# 28Pins.net
KiCad netlist of a schematic drawn in Altium Designer
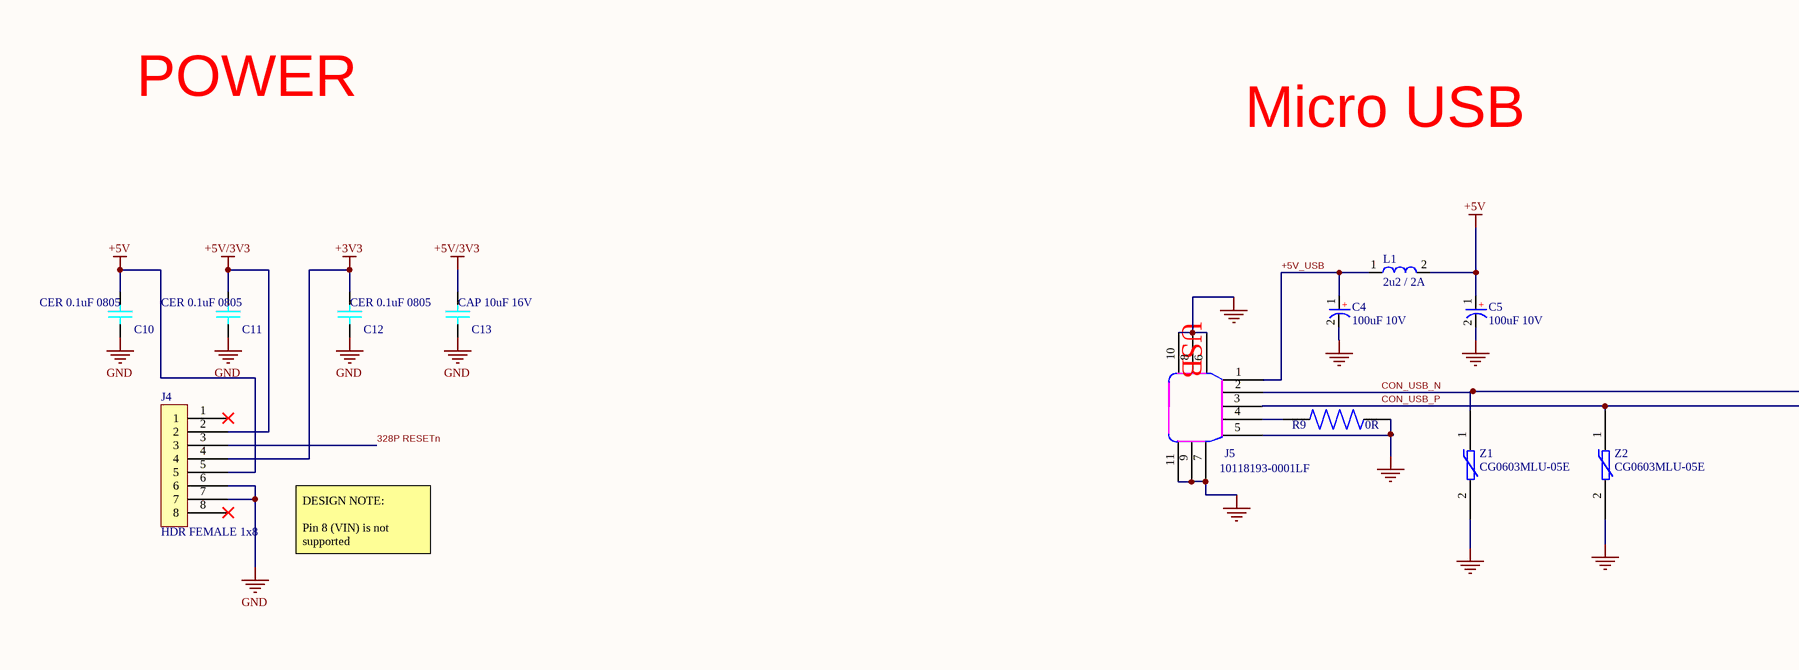
[diagram p0: 28Pins.SchDoc, top left]
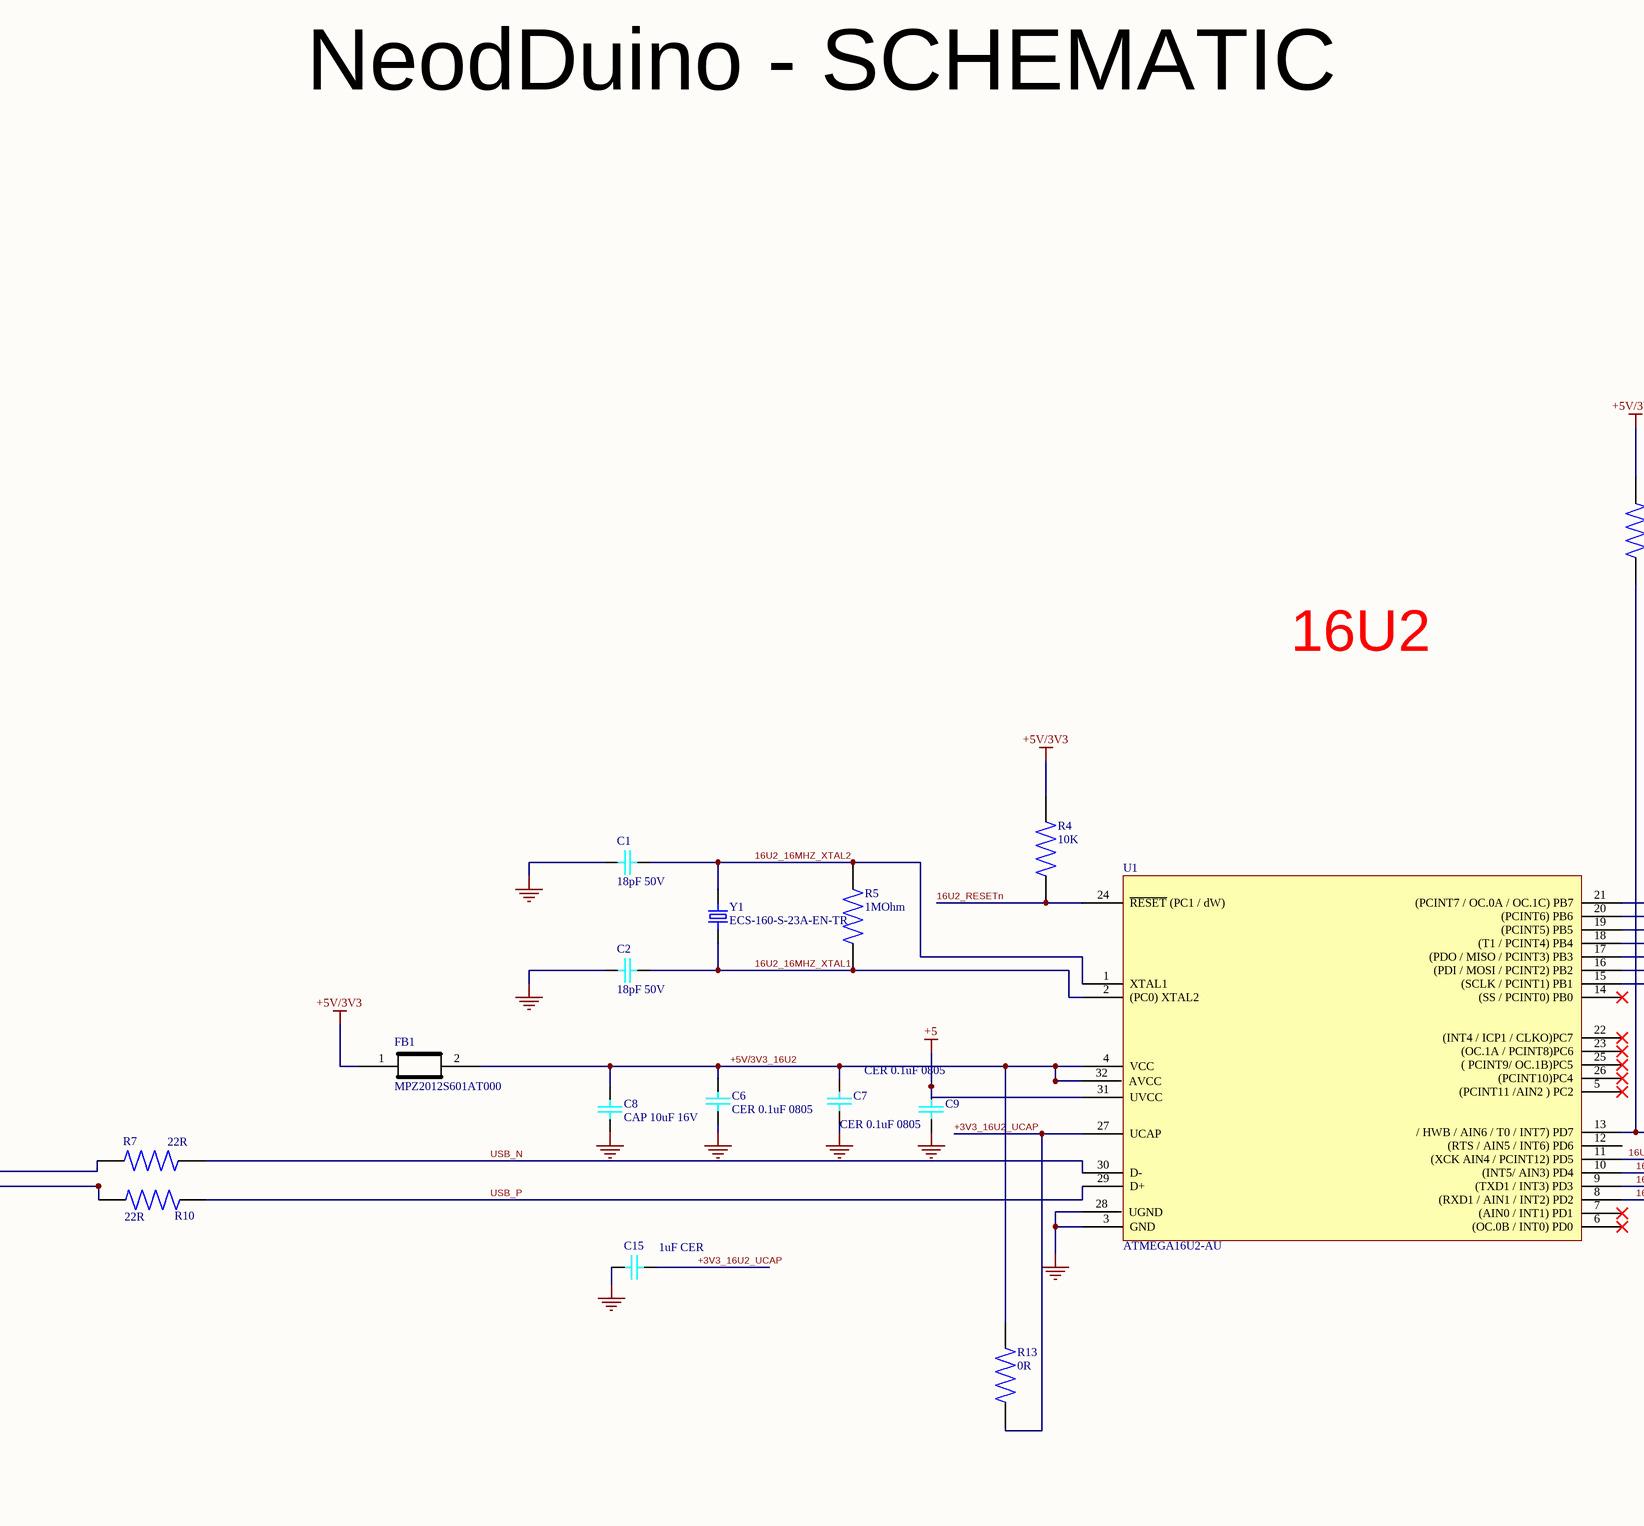
[diagram p1: 28Pins.SchDoc, top middle]
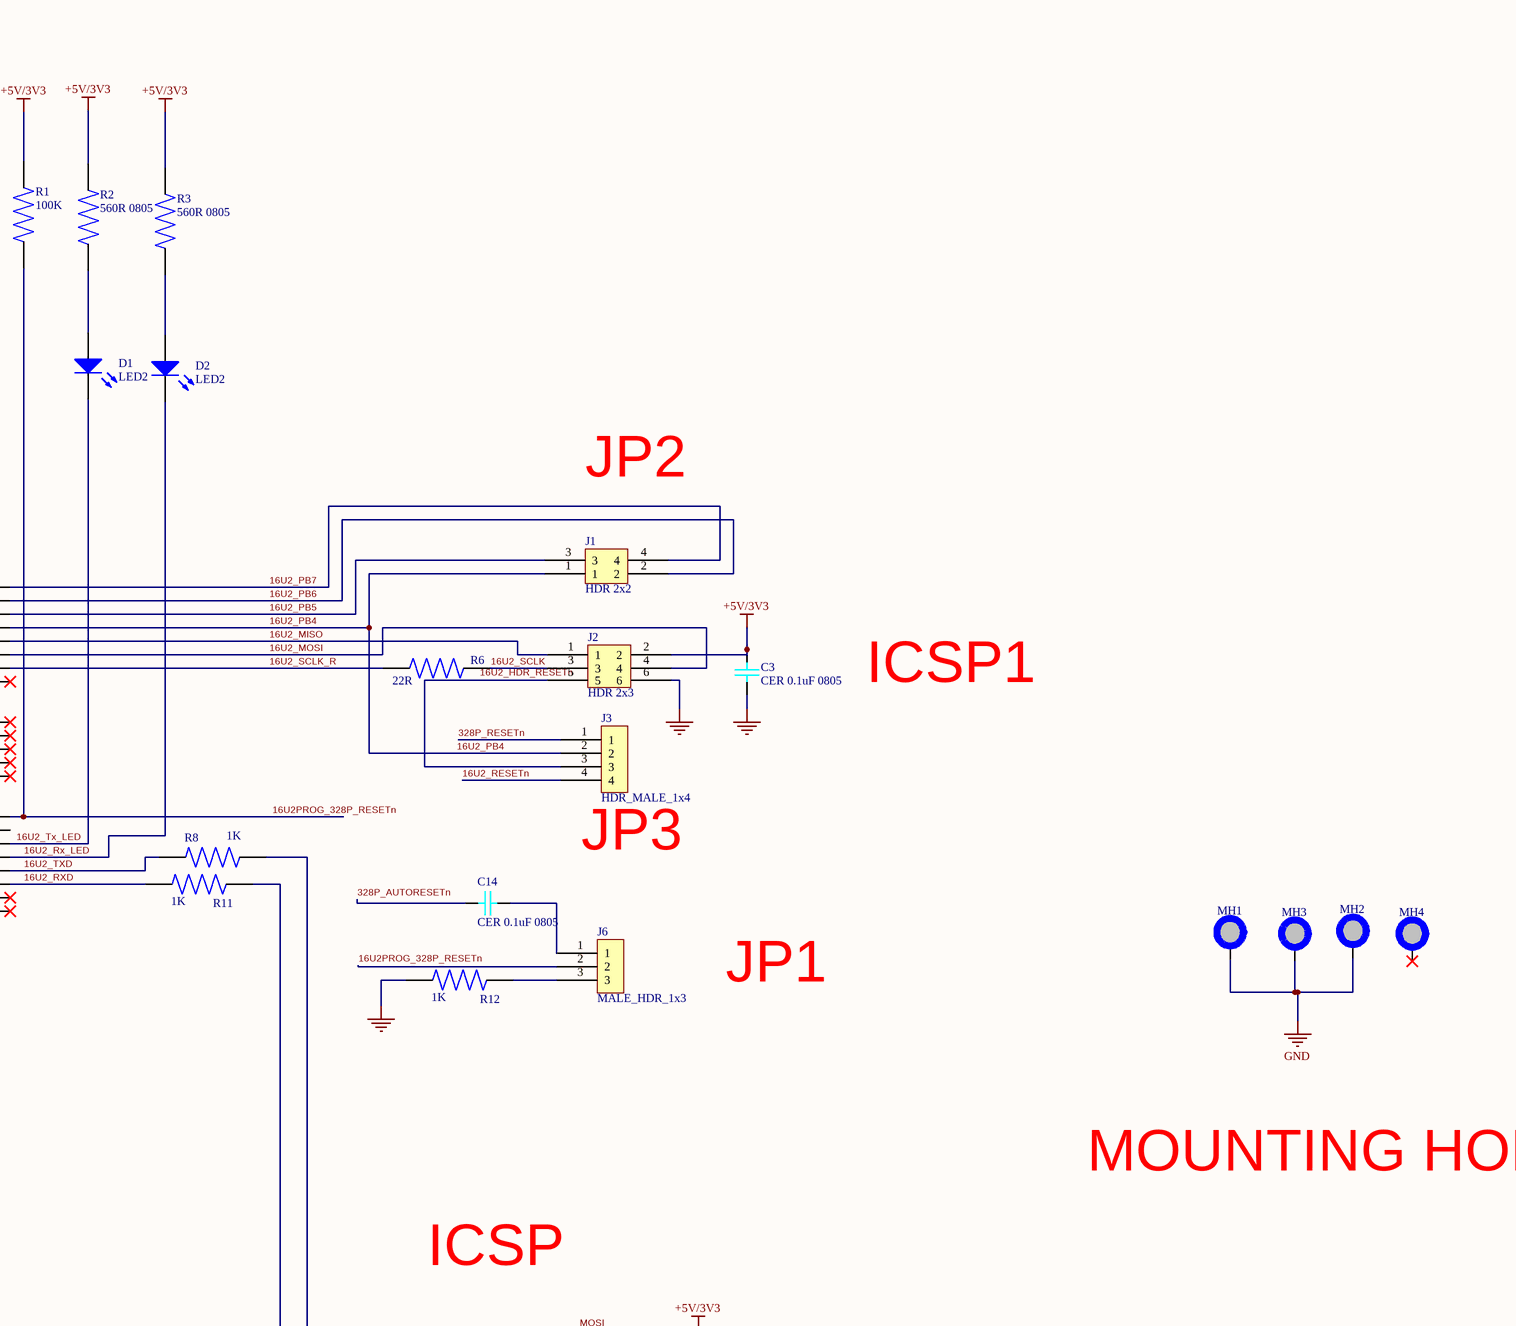
[diagram p2: 28Pins.SchDoc, top right]
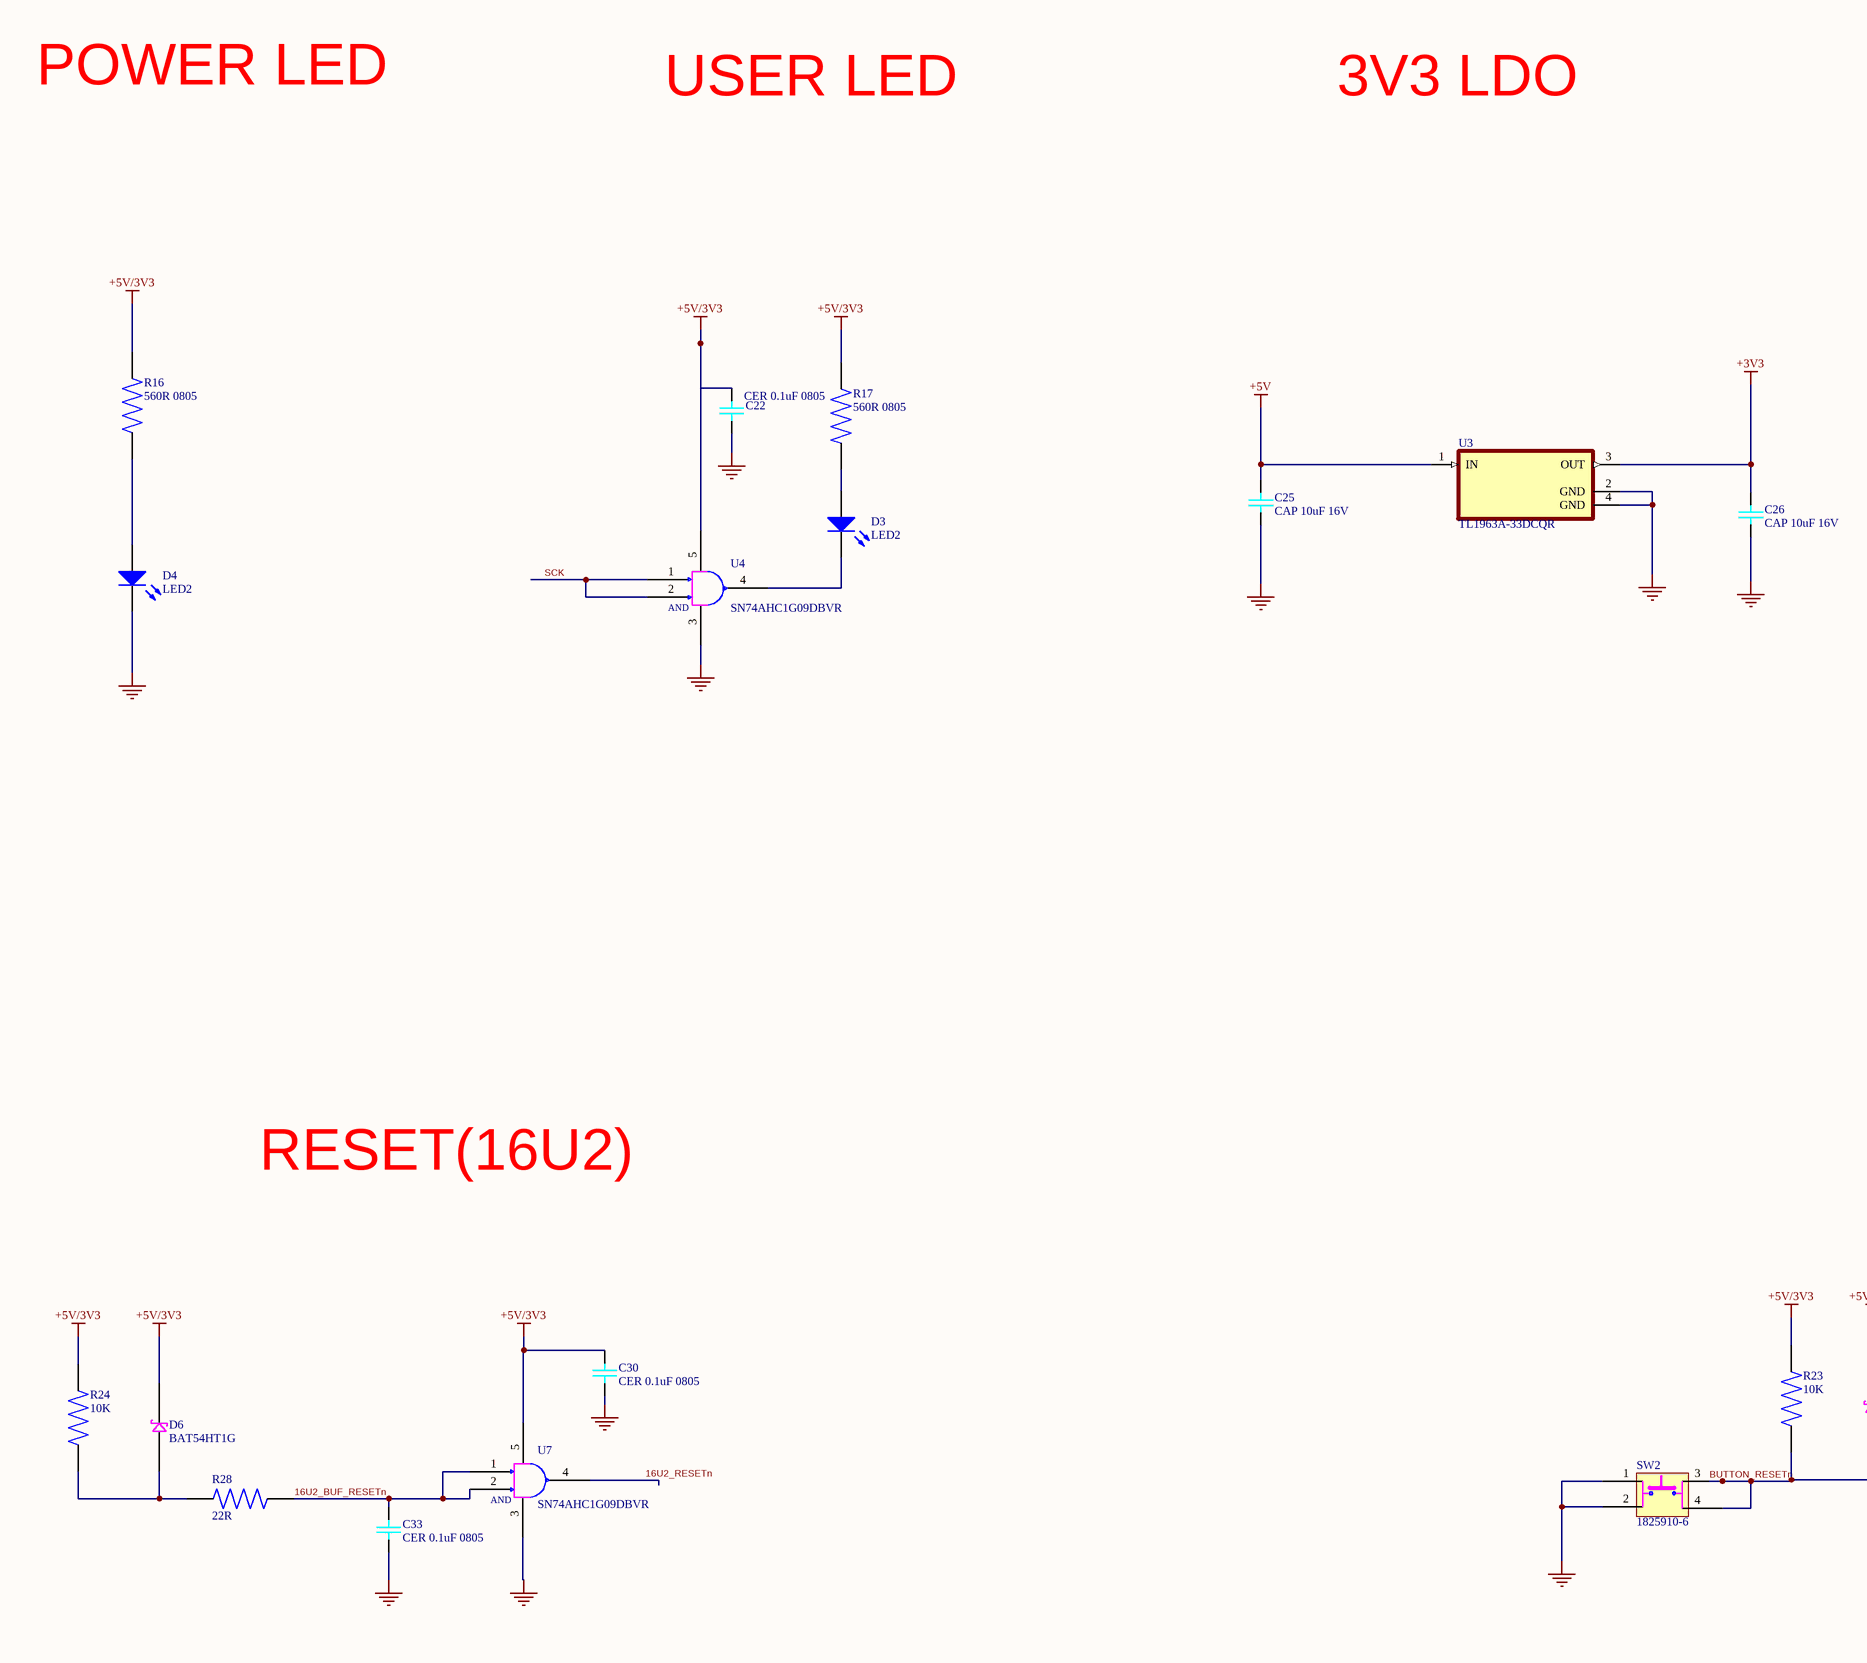
[diagram p3: 28Pins.SchDoc, bottom left]
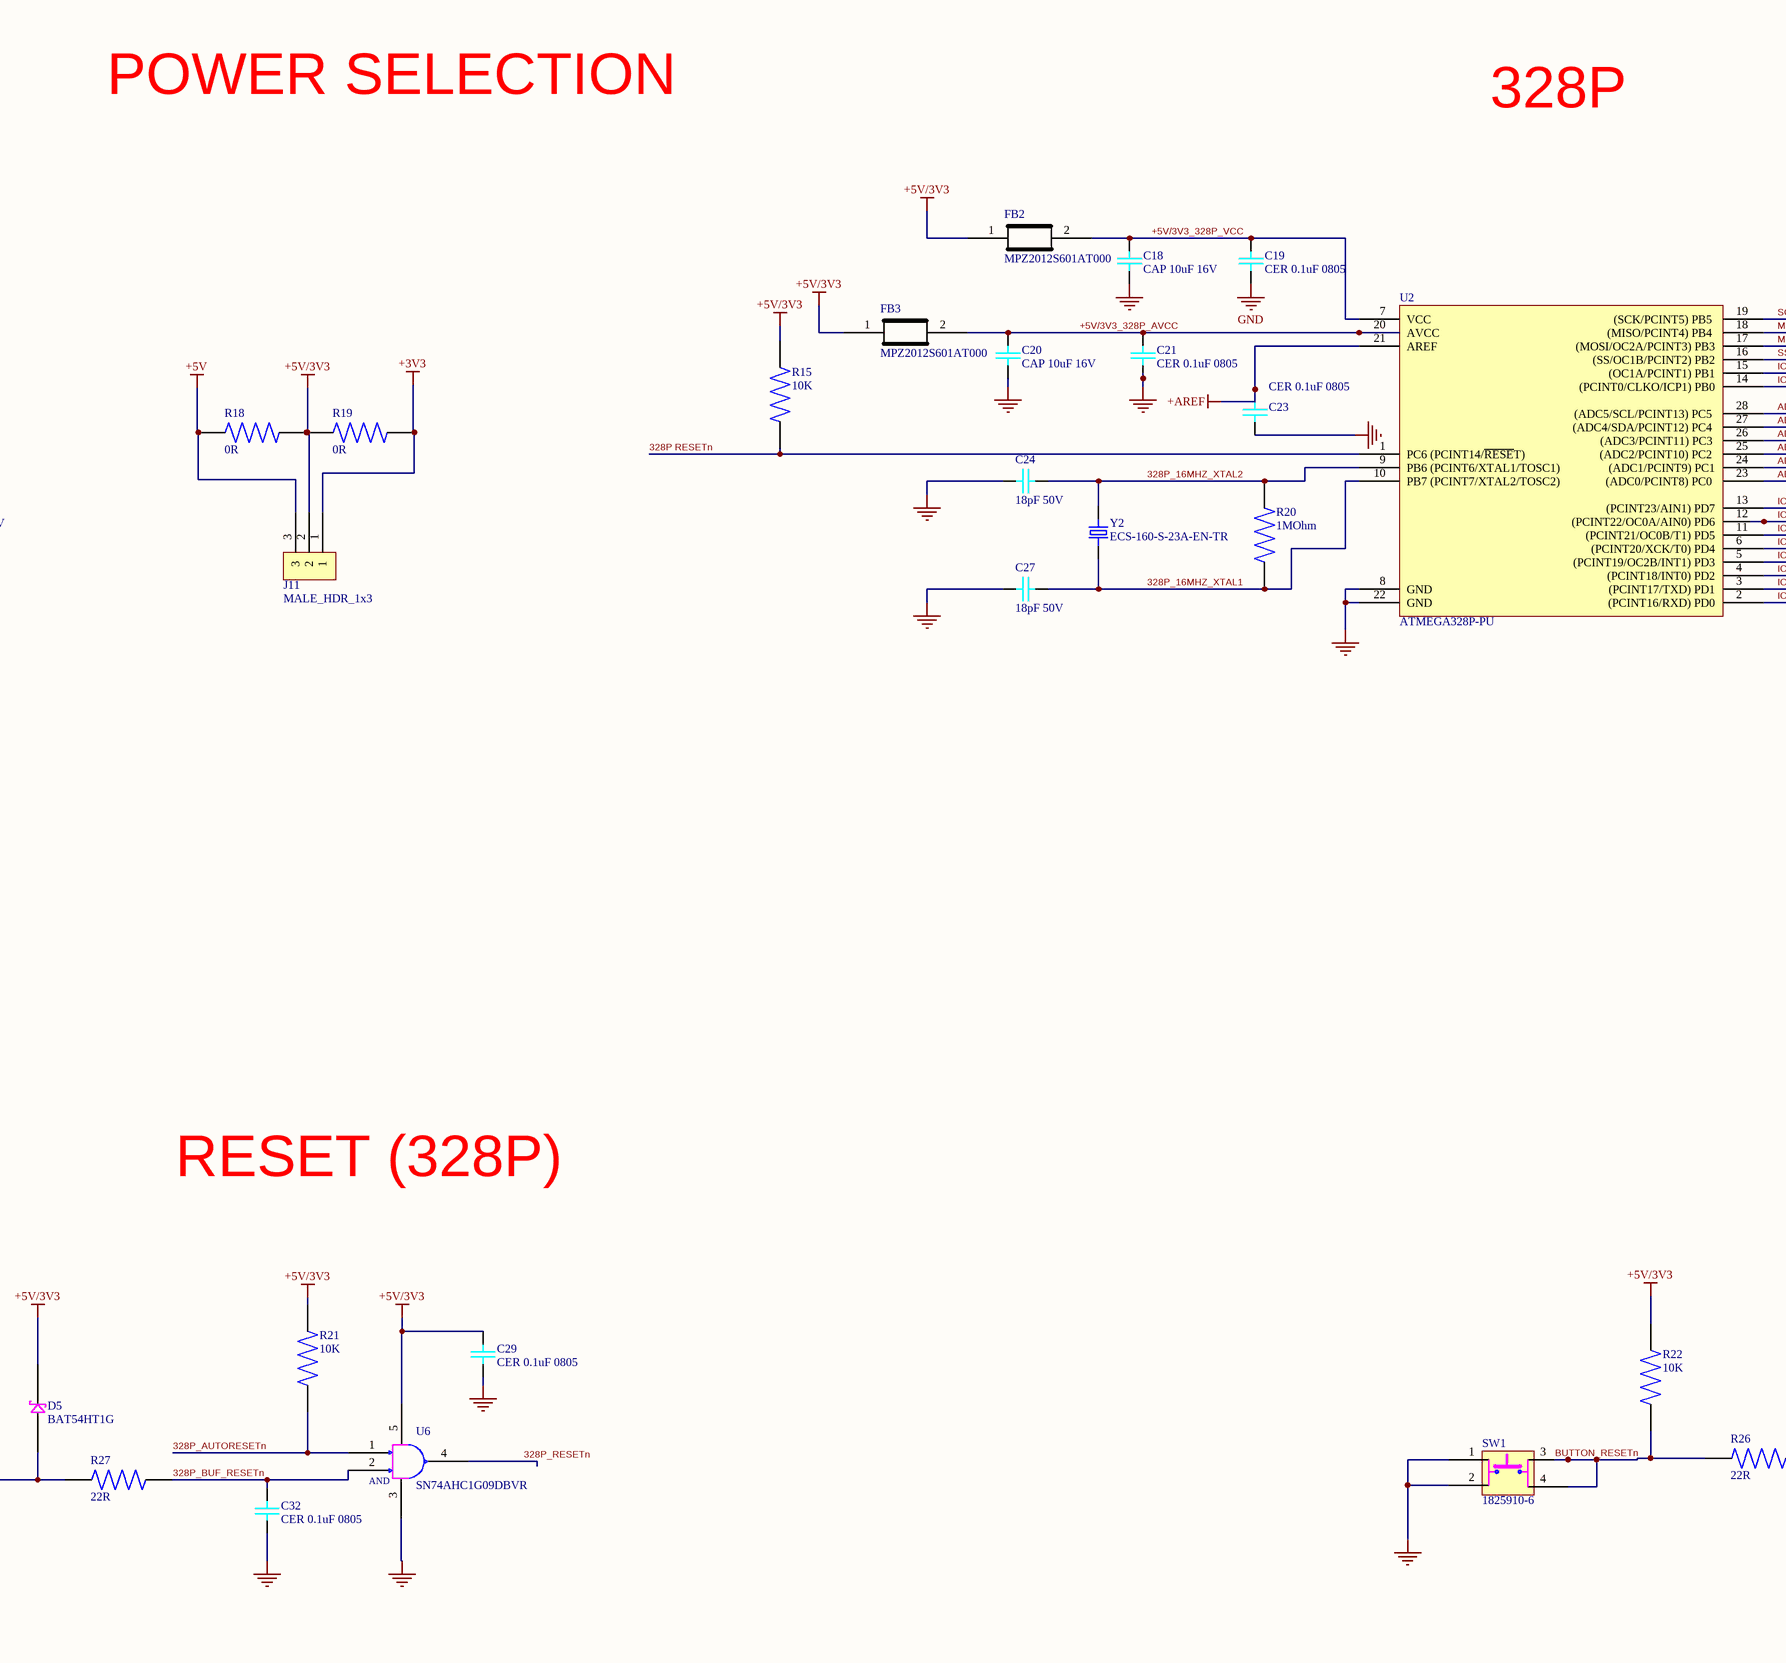
[diagram p4: 28Pins.SchDoc, bottom middle]
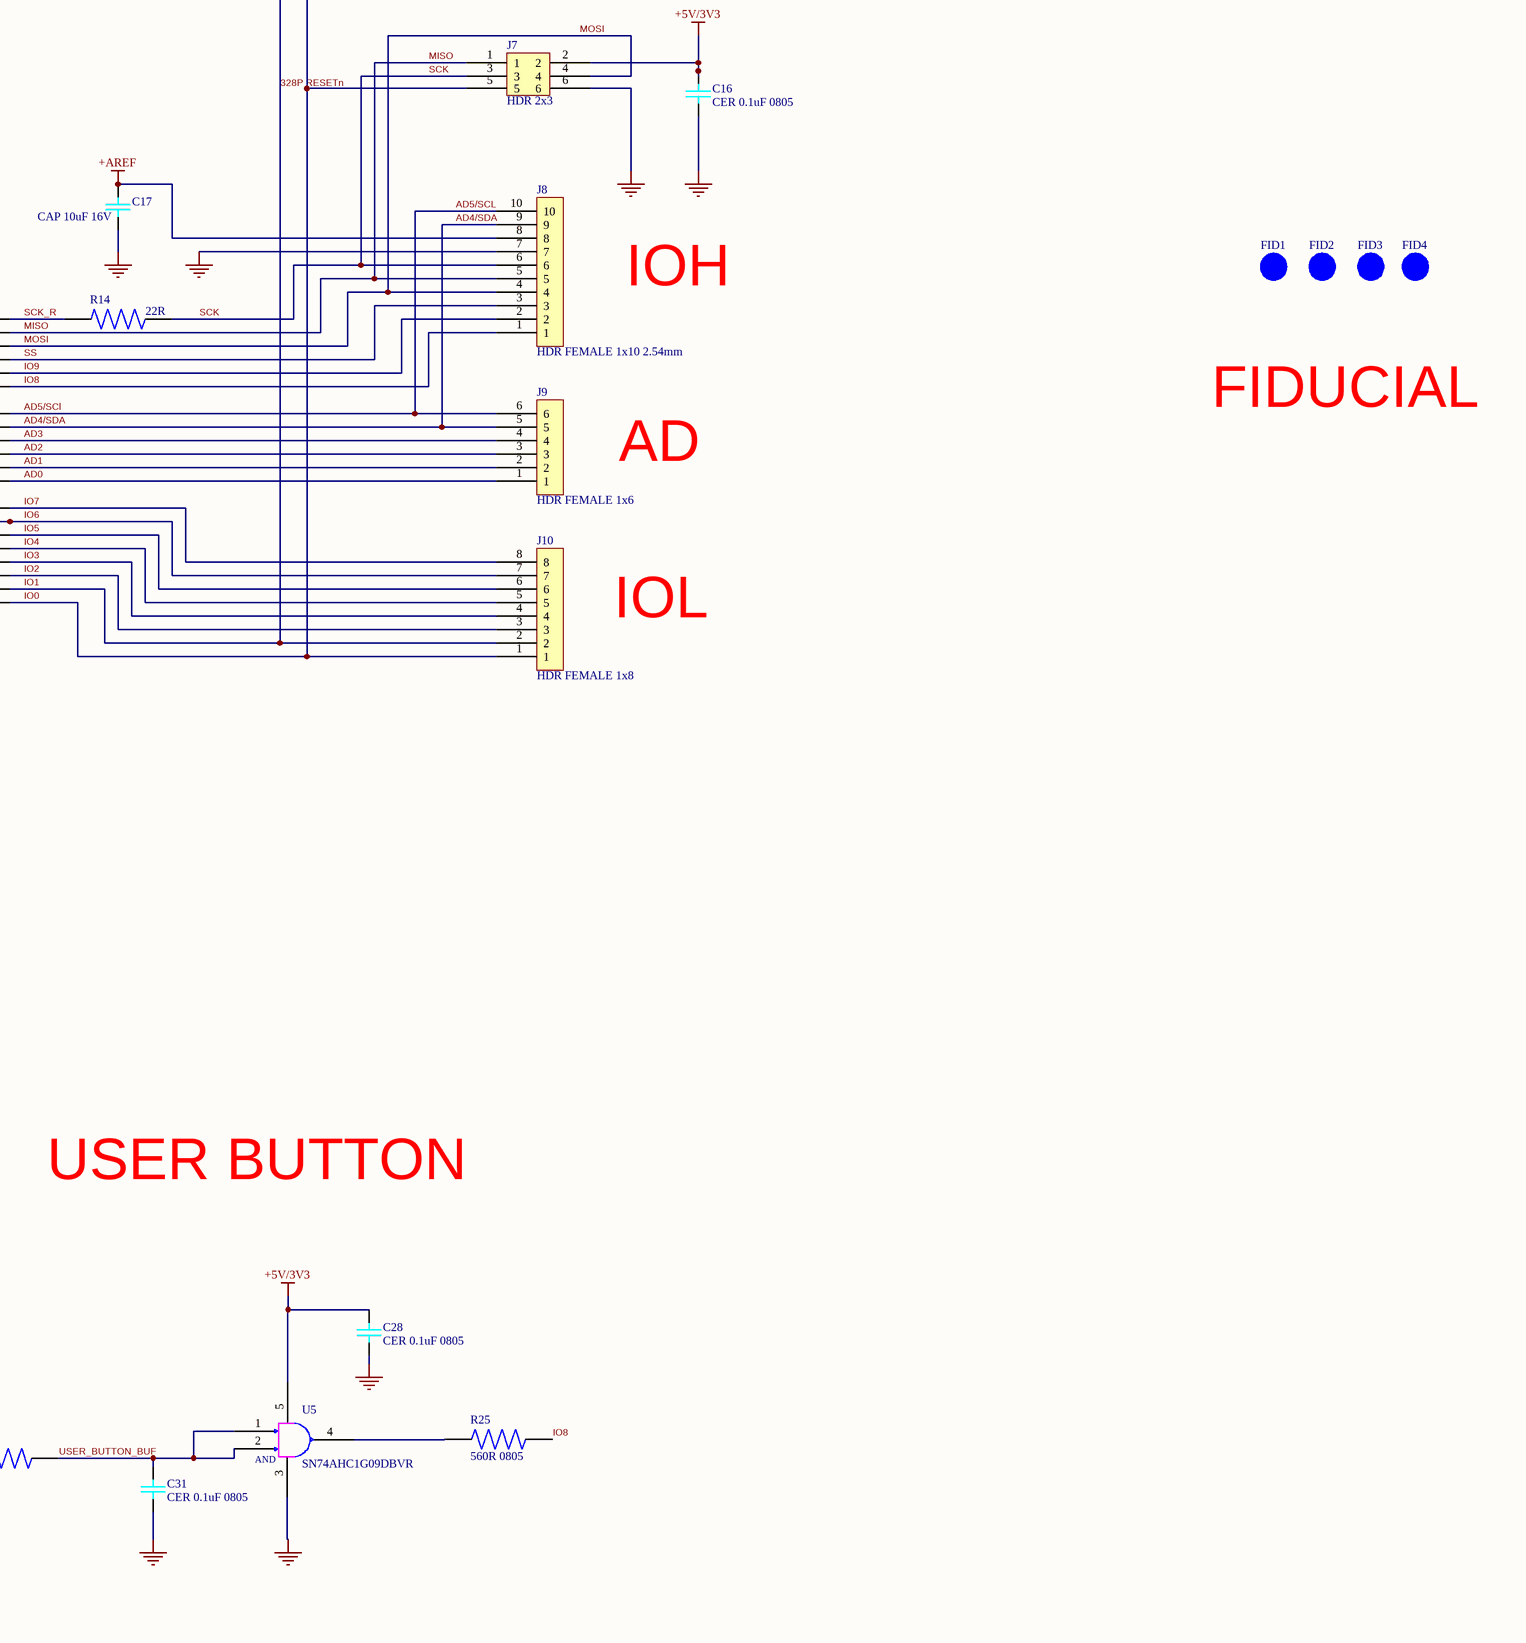
[diagram p5: 28Pins.SchDoc, bottom right]

(export (version "E")
  (design (tool "Eeschema 10.0.6"))
  (components
    (comp (ref "C1")
      (value "18pF 50V")
      (footprint "C0805")
      (fields
        (field (name "MANUFACTURER") "KEMET")
        (field (name "MANUFACTURER PART NUMBER") "C0805C180K5GACTU")
        (field (name "TOLERANCE") "10%")
      )
      (libsource (lib "28Pin_Schlib") (part "C0805C180K5GACTU"))
    )
    (comp (ref "C2")
      (value "18pF 50V")
      (footprint "C0805")
      (fields
        (field (name "MANUFACTURER") "KEMET")
        (field (name "MANUFACTURER PART NUMBER") "C0805C180K5GACTU")
        (field (name "TOLERANCE") "10%")
      )
      (libsource (lib "28Pin_Schlib") (part "C0805C180K5GACTU"))
    )
    (comp (ref "C3")
      (value "CER 0.1uF 0805")
      (footprint "C0805")
      (description "CAP CER 0.1UF 50V X7R 0805")
      (fields
        (field (name "MANUFACTURER") "TDK")
        (field (name "MANUFACTURER PART NUMBER") "CGA4J2X7R1H104K125AE")
      )
      (libsource (lib "28Pin_Schlib") (part "CGA4J2X7R1H104K125AE"))
    )
    (comp (ref "C4")
      (value "100uF 10V")
      (footprint "C_ALUMINIUM_100u")
      (description "CAP ALUM 100UF 20% 10V SMD")
      (fields
        (field (name "MANUFACTURER") "Panasonic")
        (field (name "MANUFACTURER PART NUMBER") "EEE-HA1A101P")
      )
      (libsource (lib "") (part "EEE-HA1A101P_1"))
    )
    (comp (ref "C5")
      (value "100uF 10V")
      (footprint "C_ALUMINIUM_100u")
      (description "CAP ALUM 100UF 20% 10V SMD")
      (fields
        (field (name "MANUFACTURER") "Panasonic")
        (field (name "MANUFACTURER PART NUMBER") "EEE-HA1A101P")
      )
      (libsource (lib "28Pin_Schlib") (part "EEE-HA1A101P"))
    )
    (comp (ref "C6")
      (value "CER 0.1uF 0805")
      (footprint "C0805")
      (description "CAP CER 0.1UF 50V X7R 0805")
      (fields
        (field (name "MANUFACTURER") "TDK")
        (field (name "MANUFACTURER PART NUMBER") "CGA4J2X7R1H104K125AE")
      )
      (libsource (lib "28Pin_Schlib") (part "CGA4J2X7R1H104K125AE"))
    )
    (comp (ref "C7")
      (value "CER 0.1uF 0805")
      (footprint "C0805")
      (description "CAP CER 0.1UF 50V X7R 0805")
      (fields
        (field (name "MANUFACTURER") "TDK")
        (field (name "MANUFACTURER PART NUMBER") "CGA4J2X7R1H104K125AE")
      )
      (libsource (lib "28Pin_Schlib") (part "CGA4J2X7R1H104K125AE"))
    )
    (comp (ref "C8")
      (value "CAP 10uF 16V")
      (footprint "C0805_10uF")
      (fields
        (field (name "MANUFACTURER") "TDK")
        (field (name "MANUFACTURER PART NUMBER") "CGA4J1X5R1C106K125AC")
        (field (name "TOLERANCE") "10%")
      )
      (libsource (lib "28Pin_Schlib") (part "CGA4J1X5R1C106K125AC"))
    )
    (comp (ref "C9")
      (value "CER 0.1uF 0805")
      (footprint "C0805")
      (description "CAP CER 0.1UF 50V X7R 0805")
      (fields
        (field (name "MANUFACTURER") "TDK")
        (field (name "MANUFACTURER PART NUMBER") "CGA4J2X7R1H104K125AE")
      )
      (libsource (lib "28Pin_Schlib") (part "CGA4J2X7R1H104K125AE"))
    )
    (comp (ref "C10")
      (value "CER 0.1uF 0805")
      (footprint "C0805")
      (description "CAP CER 0.1UF 50V X7R 0805")
      (fields
        (field (name "MANUFACTURER") "TDK")
        (field (name "MANUFACTURER PART NUMBER") "CGA4J2X7R1H104K125AE")
      )
      (libsource (lib "28Pin_Schlib") (part "CGA4J2X7R1H104K125AE"))
    )
    (comp (ref "C11")
      (value "CER 0.1uF 0805")
      (footprint "C0805")
      (description "CAP CER 0.1UF 50V X7R 0805")
      (fields
        (field (name "MANUFACTURER") "TDK")
        (field (name "MANUFACTURER PART NUMBER") "CGA4J2X7R1H104K125AE")
      )
      (libsource (lib "28Pin_Schlib") (part "CGA4J2X7R1H104K125AE"))
    )
    (comp (ref "C12")
      (value "CER 0.1uF 0805")
      (footprint "C0805")
      (description "CAP CER 0.1UF 50V X7R 0805")
      (fields
        (field (name "MANUFACTURER") "TDK")
        (field (name "MANUFACTURER PART NUMBER") "CGA4J2X7R1H104K125AE")
      )
      (libsource (lib "28Pin_Schlib") (part "CGA4J2X7R1H104K125AE"))
    )
    (comp (ref "C13")
      (value "CAP 10uF 16V")
      (footprint "C0805_10uF")
      (fields
        (field (name "MANUFACTURER") "TDK")
        (field (name "MANUFACTURER PART NUMBER") "CGA4J1X5R1C106K125AC")
        (field (name "TOLERANCE") "10%")
      )
      (libsource (lib "28Pin_Schlib") (part "CGA4J1X5R1C106K125AC"))
    )
    (comp (ref "C14")
      (value "CER 0.1uF 0805")
      (footprint "C0805")
      (description "CAP CER 0.1UF 50V X7R 0805")
      (fields
        (field (name "MANUFACTURER") "TDK")
        (field (name "MANUFACTURER PART NUMBER") "CGA4J2X7R1H104K125AE")
      )
      (libsource (lib "28Pin_Schlib") (part "CGA4J2X7R1H104K125AE"))
    )
    (comp (ref "C15")
      (value "1uF CER")
      (footprint "C0805")
      (description "CAP CER 1UF 25V X7R 0805")
      (fields
        (field (name "MANUFACTURER") "TDK")
        (field (name "MANUFACTURER PART NUMBER") "CGA4J3X7R1E105M125AB")
      )
      (libsource (lib "28Pin_Schlib") (part "CGA4J3X7R1E105M125AB"))
    )
    (comp (ref "C16")
      (value "CER 0.1uF 0805")
      (footprint "C0805")
      (description "CAP CER 0.1UF 50V X7R 0805")
      (fields
        (field (name "MANUFACTURER") "TDK")
        (field (name "MANUFACTURER PART NUMBER") "CGA4J2X7R1H104K125AE")
      )
      (libsource (lib "28Pin_Schlib") (part "CGA4J2X7R1H104K125AE"))
    )
    (comp (ref "C17")
      (value "CAP 10uF 16V")
      (footprint "C0805_10uF")
      (fields
        (field (name "MANUFACTURER") "TDK")
        (field (name "MANUFACTURER PART NUMBER") "CGA4J1X5R1C106K125AC")
        (field (name "TOLERANCE") "10%")
      )
      (libsource (lib "28Pin_Schlib") (part "CGA4J1X5R1C106K125AC"))
    )
    (comp (ref "C18")
      (value "CAP 10uF 16V")
      (footprint "C0805_10uF")
      (fields
        (field (name "MANUFACTURER") "TDK")
        (field (name "MANUFACTURER PART NUMBER") "CGA4J1X5R1C106K125AC")
        (field (name "TOLERANCE") "10%")
      )
      (libsource (lib "28Pin_Schlib") (part "CGA4J1X5R1C106K125AC"))
    )
    (comp (ref "C19")
      (value "CER 0.1uF 0805")
      (footprint "C0805")
      (description "CAP CER 0.1UF 50V X7R 0805")
      (fields
        (field (name "MANUFACTURER") "TDK")
        (field (name "MANUFACTURER PART NUMBER") "CGA4J2X7R1H104K125AE")
      )
      (libsource (lib "28Pin_Schlib") (part "CGA4J2X7R1H104K125AE"))
    )
    (comp (ref "C20")
      (value "CAP 10uF 16V")
      (footprint "C0805_10uF")
      (fields
        (field (name "MANUFACTURER") "TDK")
        (field (name "MANUFACTURER PART NUMBER") "CGA4J1X5R1C106K125AC")
        (field (name "TOLERANCE") "10%")
      )
      (libsource (lib "28Pin_Schlib") (part "CGA4J1X5R1C106K125AC"))
    )
    (comp (ref "C21")
      (value "CER 0.1uF 0805")
      (footprint "C0805")
      (description "CAP CER 0.1UF 50V X7R 0805")
      (fields
        (field (name "MANUFACTURER") "TDK")
        (field (name "MANUFACTURER PART NUMBER") "CGA4J2X7R1H104K125AE")
      )
      (libsource (lib "28Pin_Schlib") (part "CGA4J2X7R1H104K125AE"))
    )
    (comp (ref "C22")
      (value "CER 0.1uF 0805")
      (footprint "C0805")
      (description "CAP CER 0.1UF 50V X7R 0805")
      (fields
        (field (name "MANUFACTURER") "TDK")
        (field (name "MANUFACTURER PART NUMBER") "CGA4J2X7R1H104K125AE")
      )
      (libsource (lib "28Pin_Schlib") (part "CGA4J2X7R1H104K125AE"))
    )
    (comp (ref "C23")
      (value "CER 0.1uF 0805")
      (footprint "C0805")
      (description "CAP CER 0.1UF 50V X7R 0805")
      (fields
        (field (name "MANUFACTURER") "TDK")
        (field (name "MANUFACTURER PART NUMBER") "CGA4J2X7R1H104K125AE")
      )
      (libsource (lib "28Pin_Schlib") (part "CGA4J2X7R1H104K125AE"))
    )
    (comp (ref "C24")
      (value "18pF 50V")
      (footprint "C0805")
      (fields
        (field (name "MANUFACTURER") "KEMET")
        (field (name "MANUFACTURER PART NUMBER") "C0805C180K5GACTU")
        (field (name "TOLERANCE") "10%")
      )
      (libsource (lib "28Pin_Schlib") (part "C0805C180K5GACTU"))
    )
    (comp (ref "C25")
      (value "CAP 10uF 16V")
      (footprint "C0805_10uF")
      (fields
        (field (name "MANUFACTURER") "TDK")
        (field (name "MANUFACTURER PART NUMBER") "CGA4J1X5R1C106K125AC")
        (field (name "TOLERANCE") "10%")
      )
      (libsource (lib "28Pin_Schlib") (part "CGA4J1X5R1C106K125AC"))
    )
    (comp (ref "C26")
      (value "CAP 10uF 16V")
      (footprint "C0805_10uF")
      (fields
        (field (name "MANUFACTURER") "TDK")
        (field (name "MANUFACTURER PART NUMBER") "CGA4J1X5R1C106K125AC")
        (field (name "TOLERANCE") "10%")
      )
      (libsource (lib "28Pin_Schlib") (part "CGA4J1X5R1C106K125AC"))
    )
    (comp (ref "C27")
      (value "18pF 50V")
      (footprint "C0805")
      (fields
        (field (name "MANUFACTURER") "KEMET")
        (field (name "MANUFACTURER PART NUMBER") "C0805C180K5GACTU")
        (field (name "TOLERANCE") "10%")
      )
      (libsource (lib "28Pin_Schlib") (part "C0805C180K5GACTU"))
    )
    (comp (ref "C28")
      (value "CER 0.1uF 0805")
      (footprint "C0805")
      (description "CAP CER 0.1UF 50V X7R 0805")
      (fields
        (field (name "MANUFACTURER") "TDK")
        (field (name "MANUFACTURER PART NUMBER") "CGA4J2X7R1H104K125AE")
      )
      (libsource (lib "28Pin_Schlib") (part "CGA4J2X7R1H104K125AE"))
    )
    (comp (ref "C29")
      (value "CER 0.1uF 0805")
      (footprint "C0805")
      (description "CAP CER 0.1UF 50V X7R 0805")
      (fields
        (field (name "MANUFACTURER") "TDK")
        (field (name "MANUFACTURER PART NUMBER") "CGA4J2X7R1H104K125AE")
      )
      (libsource (lib "28Pin_Schlib") (part "CGA4J2X7R1H104K125AE"))
    )
    (comp (ref "C30")
      (value "CER 0.1uF 0805")
      (footprint "C0805")
      (description "CAP CER 0.1UF 50V X7R 0805")
      (fields
        (field (name "MANUFACTURER") "TDK")
        (field (name "MANUFACTURER PART NUMBER") "CGA4J2X7R1H104K125AE")
      )
      (libsource (lib "28Pin_Schlib") (part "CGA4J2X7R1H104K125AE"))
    )
    (comp (ref "C31")
      (value "CER 0.1uF 0805")
      (footprint "C0805")
      (description "CAP CER 0.1UF 50V X7R 0805")
      (fields
        (field (name "MANUFACTURER") "TDK")
        (field (name "MANUFACTURER PART NUMBER") "CGA4J2X7R1H104K125AE")
      )
      (libsource (lib "28Pin_Schlib") (part "CGA4J2X7R1H104K125AE"))
    )
    (comp (ref "C32")
      (value "CER 0.1uF 0805")
      (footprint "C0805")
      (description "CAP CER 0.1UF 50V X7R 0805")
      (fields
        (field (name "MANUFACTURER") "TDK")
        (field (name "MANUFACTURER PART NUMBER") "CGA4J2X7R1H104K125AE")
      )
      (libsource (lib "28Pin_Schlib") (part "CGA4J2X7R1H104K125AE"))
    )
    (comp (ref "C33")
      (value "CER 0.1uF 0805")
      (footprint "C0805")
      (description "CAP CER 0.1UF 50V X7R 0805")
      (fields
        (field (name "MANUFACTURER") "TDK")
        (field (name "MANUFACTURER PART NUMBER") "CGA4J2X7R1H104K125AE")
      )
      (libsource (lib "28Pin_Schlib") (part "CGA4J2X7R1H104K125AE"))
    )
    (comp (ref "D1")
      (value "LED2")
      (footprint "3.2X1.6X1.1")
      (description "Typical RED, GREEN, YELLOW, AMBER GaAs LED")
      (fields (field (name "PUBLISHER") "Altium Limited"))
      (libsource (lib "Miscellaneous Devices") (part "LED2"))
    )
    (comp (ref "D2")
      (value "LED2")
      (footprint "3.2X1.6X1.1")
      (description "Typical RED, GREEN, YELLOW, AMBER GaAs LED")
      (fields (field (name "PUBLISHER") "Altium Limited"))
      (libsource (lib "Miscellaneous Devices") (part "LED2"))
    )
    (comp (ref "D3")
      (value "LED2")
      (footprint "3.2X1.6X1.1")
      (description "Typical RED, GREEN, YELLOW, AMBER GaAs LED")
      (fields (field (name "PUBLISHER") "Altium Limited"))
      (libsource (lib "Miscellaneous Devices") (part "LED2"))
    )
    (comp (ref "D4")
      (value "LED2")
      (footprint "3.2X1.6X1.1")
      (description "Typical RED, GREEN, YELLOW, AMBER GaAs LED")
      (fields (field (name "PUBLISHER") "Altium Limited"))
      (libsource (lib "Miscellaneous Devices") (part "LED2"))
    )
    (comp (ref "D5")
      (value "BAT54HT1G")
      (footprint "SOD323_DIODE")
      (description "Small Signal Schottky Diode, Single, 30 V, 200 mA, 800 mV, 600 mA, 150 C ;RoHS Compliant: Yes")
      (fields (field (name "MANUFACTURER") "ON Semiconductor / Fairchild"))
      (libsource (lib "28Pin_Schlib") (part "BAT54HT1G"))
    )
    (comp (ref "D6")
      (value "BAT54HT1G")
      (footprint "SOD323_DIODE")
      (description "Small Signal Schottky Diode, Single, 30 V, 200 mA, 800 mV, 600 mA, 150 C ;RoHS Compliant: Yes")
      (fields (field (name "MANUFACTURER") "ON Semiconductor / Fairchild"))
      (libsource (lib "28Pin_Schlib") (part "BAT54HT1G"))
    )
    (comp (ref "FB1")
      (value "MPZ2012S601AT000")
      (footprint "C0805")
      (description "FERRITE BEAD 600 OHM 0805 1LN")
      (fields (field (name "MANUFACTURER") "TDK"))
      (libsource (lib "28Pin_Schlib") (part "MPZ2012S601AT000"))
    )
    (comp (ref "FB2")
      (value "MPZ2012S601AT000")
      (footprint "C0805")
      (description "FERRITE BEAD 600 OHM 0805 1LN")
      (fields (field (name "MANUFACTURER") "TDK"))
      (libsource (lib "28Pin_Schlib") (part "MPZ2012S601AT000"))
    )
    (comp (ref "FB3")
      (value "MPZ2012S601AT000")
      (footprint "C0805")
      (description "FERRITE BEAD 600 OHM 0805 1LN")
      (fields (field (name "MANUFACTURER") "TDK"))
      (libsource (lib "28Pin_Schlib") (part "MPZ2012S601AT000"))
    )
    (comp (ref "FID1")
      (value "FID_1MMC")
      (footprint "FID_40x120MM")
      (description "Fiducial 40mil dia, 120mil mask")
      (libsource (lib "28Pin_Schlib") (part "FID_1MM"))
    )
    (comp (ref "FID2")
      (value "FID_1MMC")
      (footprint "FID_40x120MM")
      (description "Fiducial 40mil dia, 120mil mask")
      (libsource (lib "28Pin_Schlib") (part "FID_1MM"))
    )
    (comp (ref "FID3")
      (value "FID_1MMC")
      (footprint "FID_40x120MM")
      (description "Fiducial 40mil dia, 120mil mask")
      (libsource (lib "28Pin_Schlib") (part "FID_1MM"))
    )
    (comp (ref "FID4")
      (value "FID_1MMC")
      (footprint "FID_40x120MM")
      (description "Fiducial 40mil dia, 120mil mask")
      (libsource (lib "28Pin_Schlib") (part "FID_1MM"))
    )
    (comp (ref "J1")
      (value "HDR 2x2")
      (footprint "HDR_2x2_2.54MM")
      (description "02+02 DIL Vert Pin Hdr")
      (fields (field (name "MANUFACTURER") "Harwin") (field (name "MANUFACTURER PART NUMBER") "M20-9980245"))
      (libsource (lib "28Pin_Schlib") (part "M20-9980245"))
    )
    (comp (ref "J2")
      (value "HDR 2x3")
      (footprint "HDR_2x3_2.54MM")
      (description "Conn Unshrouded Header HDR 6 POS 2.54mm Solder ST Thru-Hole Bag")
      (fields (field (name "MANUFACTURER") "Harwin") (field (name "MANUFACTURER PART NUMBER") "M20-9980346"))
      (libsource (lib "28Pin_Schlib") (part "M20-9980346"))
    )
    (comp (ref "J3")
      (value "HDR_MALE_1x4")
      (footprint "HDR_MALE_1x4")
      (description "4 Way Sil Horiz Smt P/hdr Rohs Compliant: Yes")
      (fields (field (name "MANUFACTURER") "Harwin") (field (name "MANUFACTURER PART NUMBER") "M20-8890445"))
      (libsource (lib "28Pin_Schlib") (part "M20-8890445"))
    )
    (comp (ref "J4")
      (value "HDR FEMALE 1x8")
      (footprint "HDR_FEMALE_1x8")
      (fields (field (name "MANUFACTURER") "Harwin") (field (name "MANUFACTURER PART NUMBER") "M20-7821046"))
      (libsource (lib "") (part "M20-7821046_1"))
    )
    (comp (ref "J5")
      (value "10118193-0001LF")
      (footprint "USB_micro")
      (description "CONN USB MICRO B RECPT SMT R/A")
      (fields (field (name "MANUFACTURER") "Amphenol ICC / FCI"))
      (libsource (lib "28Pin_Schlib") (part "10118193-0001LF"))
    )
    (comp (ref "J6")
      (value "MALE_HDR_1x3")
      (footprint "HDR_MALE_1x3")
      (fields (field (name "MANUFACTURER") "Harwin") (field (name "MANUFACTURER PART NUMBER") "M20-9990345"))
      (libsource (lib "") (part "M20-9990345_1"))
    )
    (comp (ref "J7")
      (value "HDR 2x3")
      (footprint "HDR_2x3_2.54MM")
      (description "Conn Unshrouded Header HDR 6 POS 2.54mm Solder ST Thru-Hole Bag")
      (fields (field (name "MANUFACTURER") "Harwin") (field (name "MANUFACTURER PART NUMBER") "M20-9980346"))
      (libsource (lib "28Pin_Schlib") (part "M20-9980346"))
    )
    (comp (ref "J8")
      (value "HDR FEMALE 1x10 2.54mm")
      (footprint "HDR_FEMALE_1x10")
      (libsource (lib "28Pin_Schlib") (part "952-3580-ND (female header 10pin)"))
    )
    (comp (ref "J9")
      (value "HDR FEMALE 1x6")
      (footprint "HDR_FEMALE_1x6")
      (description "06-WAY SIL VERT SOCKET L/FREE")
      (fields (field (name "MANUFACTURER") "Harwin") (field (name "MANUFACTURER PART NUMBER") "M20-7820646"))
      (libsource (lib "28Pin_Schlib") (part "M20-7820646"))
    )
    (comp (ref "J10")
      (value "HDR FEMALE 1x8")
      (footprint "HDR_FEMALE_1x8")
      (fields (field (name "MANUFACTURER") "Harwin") (field (name "MANUFACTURER PART NUMBER") "M20-7821046"))
      (libsource (lib "28Pin_Schlib") (part "M20-7821046"))
    )
    (comp (ref "J11")
      (value "MALE_HDR_1x3")
      (footprint "HDR_MALE_1x3")
      (fields (field (name "MANUFACTURER") "Harwin") (field (name "MANUFACTURER PART NUMBER") "M20-9990345"))
      (libsource (lib "28Pin_Schlib") (part "M20-9990345"))
    )
    (comp (ref "L1")
      (value "2u2 / 2A")
      (footprint "CL10INDUCTOR")
      (description "FIXED IND 2.2UH 2A 80 MOHM SMD")
      (fields
        (field (name "MANUFACTURER") "KEMET")
        (field (name "MANUFACTURER PART NUMBER") "L1210R2R2MDWIT")
      )
      (libsource (lib "28Pin_Schlib") (part "L1210R2R2MDWIT"))
    )
    (comp (ref "MH1")
      (value "MH_7.4_3.3MM")
      (footprint "MH_7.4MM_3.2MMDRILL_NOPT")
      (description "Mounting hole 7.4mm diameter, 3.4 mm drill")
      (libsource (lib "28Pin_Schlib") (part "mounting_holes"))
    )
    (comp (ref "MH2")
      (value "MH_7.4_3.3MM")
      (footprint "MH_7.4MM_3.2MMDRILL_NOPT")
      (description "Mounting hole 7.4mm diameter, 3.4 mm drill")
      (libsource (lib "28Pin_Schlib") (part "mounting_holes"))
    )
    (comp (ref "MH3")
      (value "MH_7.4_3.3MM")
      (footprint "MH_7.4MM_3.2MMDRILL_NOPT")
      (description "Mounting hole 7.4mm diameter, 3.4 mm drill")
      (libsource (lib "28Pin_Schlib") (part "mounting_holes"))
    )
    (comp (ref "MH4")
      (value "MH_7.4_3.3MM")
      (footprint "MH_7.4MM_3.2MMDRILL_NOPT")
      (description "Mounting hole 7.4mm diameter, 3.4 mm drill")
      (libsource (lib "28Pin_Schlib") (part "mounting_holes"))
    )
    (comp (ref "R1")
      (value "100K")
      (footprint "RESC2012X65N")
      (description "Res Thick Film 0805 100K Ohm 1% 1/8W ±100ppm/°C Molded SMD SMD Paper T/R")
      (fields
        (field (name "MANUFACTURER") "Yageo")
        (field (name "MANUFACTURER PART NUMBER") "AC0805FR-07100KL")
      )
      (libsource (lib "28Pin_Schlib") (part "AC0805FR-07100KL"))
    )
    (comp (ref "R2")
      (value "560R 0805")
      (footprint "RESC2012X65N")
      (description "RES SMD 560 OHM 1% 1/8W 0805")
      (fields
        (field (name "MANUFACTURER") "Yageo")
        (field (name "MANUFACTURER PART NUMBER") "RT0805FRE07560RL")
      )
      (libsource (lib "28Pin_Schlib") (part "RT0805FRE07560RL"))
    )
    (comp (ref "R3")
      (value "560R 0805")
      (footprint "RESC2012X65N")
      (description "RES SMD 560 OHM 1% 1/8W 0805")
      (fields
        (field (name "MANUFACTURER") "Yageo")
        (field (name "MANUFACTURER PART NUMBER") "RT0805FRE07560RL")
      )
      (libsource (lib "28Pin_Schlib") (part "RT0805FRE07560RL"))
    )
    (comp (ref "R4")
      (value "10K")
      (footprint "RESC2012X65N")
      (description "RES SMD 10K OHM 1% 1/8W 0805")
      (fields
        (field (name "MANUFACTURER") "Yageo")
        (field (name "MANUFACTURER PART NUMBER") "AC0805FR-0710KL")
      )
      (libsource (lib "28Pin_Schlib") (part "AC0805FR-0710KL"))
    )
    (comp (ref "R5")
      (value "1MOhm")
      (footprint "RESC2012X65N")
      (fields (field (name "MP") "RMCF0805FG1M00"))
      (libsource (lib "RMCF0805FG1M00") (part "RMCF0805FG1M00"))
    )
    (comp (ref "R6")
      (value "22R")
      (footprint "RESC2012X65N")
      (description "Resistor;  Thick Film;  Res 22 Ohms;  Pwr-Rtg0.125 W;  Tol 1%;  SMT;  0805")
      (fields
        (field (name "MANUFACTURER") "TE Connectivity")
        (field (name "MANUFACTURER PART NUMBER") "CRG0805F22R")
      )
      (libsource (lib "28Pin_Schlib") (part "CRG0805F22R"))
    )
    (comp (ref "R7")
      (value "22R")
      (footprint "RESC2012X65N")
      (description "Resistor;  Thick Film;  Res 22 Ohms;  Pwr-Rtg0.125 W;  Tol 1%;  SMT;  0805")
      (fields
        (field (name "MANUFACTURER") "TE Connectivity")
        (field (name "MANUFACTURER PART NUMBER") "CRG0805F22R")
      )
      (libsource (lib "28Pin_Schlib") (part "CRG0805F22R"))
    )
    (comp (ref "R8")
      (value "1K")
      (footprint "RESC2012X65N")
      (fields
        (field (name "MANUFACTURER") "TE Connectivity Neohm")
        (field (name "MANUFACTURER PART NUMBER") "CPF0805B1K0E1")
        (field (name "TOLERANCE") "0.1%")
      )
      (libsource (lib "28Pin_Schlib") (part "CPF0805B1K0E1"))
    )
    (comp (ref "R9")
      (value "0R")
      (footprint "RESC2012X65N")
      (description "Res Thick Film 0805 0 Ohm Molded SMD Paper T/R")
      (fields
        (field (name "MANUFACTURER") "Yageo")
        (field (name "MANUFACTURER PART NUMBER") "RC0805JR-130RL")
      )
      (libsource (lib "28Pin_Schlib") (part "RC0805JR-130RL"))
    )
    (comp (ref "R10")
      (value "22R")
      (footprint "RESC2012X65N")
      (description "Resistor;  Thick Film;  Res 22 Ohms;  Pwr-Rtg0.125 W;  Tol 1%;  SMT;  0805")
      (fields
        (field (name "MANUFACTURER") "TE Connectivity")
        (field (name "MANUFACTURER PART NUMBER") "CRG0805F22R")
      )
      (libsource (lib "28Pin_Schlib") (part "CRG0805F22R"))
    )
    (comp (ref "R11")
      (value "1K")
      (footprint "RESC2012X65N")
      (fields
        (field (name "MANUFACTURER") "TE Connectivity Neohm")
        (field (name "MANUFACTURER PART NUMBER") "CPF0805B1K0E1")
        (field (name "TOLERANCE") "0.1%")
      )
      (libsource (lib "28Pin_Schlib") (part "CPF0805B1K0E1"))
    )
    (comp (ref "R12")
      (value "1K")
      (footprint "RESC2012X65N")
      (fields
        (field (name "MANUFACTURER") "TE Connectivity Neohm")
        (field (name "MANUFACTURER PART NUMBER") "CPF0805B1K0E1")
        (field (name "TOLERANCE") "0.1%")
      )
      (libsource (lib "28Pin_Schlib") (part "CPF0805B1K0E1"))
    )
    (comp (ref "R13")
      (value "0R")
      (footprint "RESC2012X65N")
      (description "Res Thick Film 0805 0 Ohm Molded SMD Paper T/R")
      (fields
        (field (name "MANUFACTURER") "Yageo")
        (field (name "MANUFACTURER PART NUMBER") "RC0805JR-130RL")
      )
      (libsource (lib "28Pin_Schlib") (part "RC0805JR-130RL"))
    )
    (comp (ref "R14")
      (value "22R")
      (footprint "RESC2012X65N")
      (description "Resistor;  Thick Film;  Res 22 Ohms;  Pwr-Rtg0.125 W;  Tol 1%;  SMT;  0805")
      (fields
        (field (name "MANUFACTURER") "TE Connectivity")
        (field (name "MANUFACTURER PART NUMBER") "CRG0805F22R")
      )
      (libsource (lib "28Pin_Schlib") (part "CRG0805F22R"))
    )
    (comp (ref "R15")
      (value "10K")
      (footprint "RESC2012X65N")
      (description "RES SMD 10K OHM 1% 1/8W 0805")
      (fields
        (field (name "MANUFACTURER") "Yageo")
        (field (name "MANUFACTURER PART NUMBER") "AC0805FR-0710KL")
      )
      (libsource (lib "28Pin_Schlib") (part "AC0805FR-0710KL"))
    )
    (comp (ref "R16")
      (value "560R 0805")
      (footprint "RESC2012X65N")
      (description "RES SMD 560 OHM 1% 1/8W 0805")
      (fields
        (field (name "MANUFACTURER") "Yageo")
        (field (name "MANUFACTURER PART NUMBER") "RT0805FRE07560RL")
      )
      (libsource (lib "28Pin_Schlib") (part "RT0805FRE07560RL"))
    )
    (comp (ref "R17")
      (value "560R 0805")
      (footprint "RESC2012X65N")
      (description "RES SMD 560 OHM 1% 1/8W 0805")
      (fields
        (field (name "MANUFACTURER") "Yageo")
        (field (name "MANUFACTURER PART NUMBER") "RT0805FRE07560RL")
      )
      (libsource (lib "28Pin_Schlib") (part "RT0805FRE07560RL"))
    )
    (comp (ref "R18")
      (value "0R")
      (footprint "RESC2012X65N")
      (description "Res Thick Film 0805 0 Ohm Molded SMD Paper T/R")
      (fields
        (field (name "MANUFACTURER") "Yageo")
        (field (name "MANUFACTURER PART NUMBER") "RC0805JR-130RL")
      )
      (libsource (lib "28Pin_Schlib") (part "RC0805JR-130RL"))
    )
    (comp (ref "R19")
      (value "0R")
      (footprint "RESC2012X65N")
      (description "Res Thick Film 0805 0 Ohm Molded SMD Paper T/R")
      (fields
        (field (name "MANUFACTURER") "Yageo")
        (field (name "MANUFACTURER PART NUMBER") "RC0805JR-130RL")
      )
      (libsource (lib "28Pin_Schlib") (part "RC0805JR-130RL"))
    )
    (comp (ref "R20")
      (value "1MOhm")
      (footprint "RESC2012X65N")
      (fields (field (name "MP") "RMCF0805FG1M00"))
      (libsource (lib "RMCF0805FG1M00") (part "RMCF0805FG1M00"))
    )
    (comp (ref "R21")
      (value "10K")
      (footprint "RESC2012X65N")
      (description "RES SMD 10K OHM 1% 1/8W 0805")
      (fields
        (field (name "MANUFACTURER") "Yageo")
        (field (name "MANUFACTURER PART NUMBER") "AC0805FR-0710KL")
      )
      (libsource (lib "28Pin_Schlib") (part "AC0805FR-0710KL"))
    )
    (comp (ref "R22")
      (value "10K")
      (footprint "RESC2012X65N")
      (description "RES SMD 10K OHM 1% 1/8W 0805")
      (fields
        (field (name "MANUFACTURER") "Yageo")
        (field (name "MANUFACTURER PART NUMBER") "AC0805FR-0710KL")
      )
      (libsource (lib "28Pin_Schlib") (part "AC0805FR-0710KL"))
    )
    (comp (ref "R23")
      (value "10K")
      (footprint "RESC2012X65N")
      (description "RES SMD 10K OHM 1% 1/8W 0805")
      (fields
        (field (name "MANUFACTURER") "Yageo")
        (field (name "MANUFACTURER PART NUMBER") "AC0805FR-0710KL")
      )
      (libsource (lib "28Pin_Schlib") (part "AC0805FR-0710KL"))
    )
    (comp (ref "R24")
      (value "10K")
      (footprint "RESC2012X65N")
      (description "RES SMD 10K OHM 1% 1/8W 0805")
      (fields
        (field (name "MANUFACTURER") "Yageo")
        (field (name "MANUFACTURER PART NUMBER") "AC0805FR-0710KL")
      )
      (libsource (lib "28Pin_Schlib") (part "AC0805FR-0710KL"))
    )
    (comp (ref "R25")
      (value "560R 0805")
      (footprint "RESC2012X65N")
      (description "RES SMD 560 OHM 1% 1/8W 0805")
      (fields
        (field (name "MANUFACTURER") "Yageo")
        (field (name "MANUFACTURER PART NUMBER") "RT0805FRE07560RL")
      )
      (libsource (lib "28Pin_Schlib") (part "RT0805FRE07560RL"))
    )
    (comp (ref "R26")
      (value "22R")
      (footprint "RESC2012X65N")
      (description "Resistor;  Thick Film;  Res 22 Ohms;  Pwr-Rtg0.125 W;  Tol 1%;  SMT;  0805")
      (fields
        (field (name "MANUFACTURER") "TE Connectivity")
        (field (name "MANUFACTURER PART NUMBER") "CRG0805F22R")
      )
      (libsource (lib "28Pin_Schlib") (part "CRG0805F22R"))
    )
    (comp (ref "R27")
      (value "22R")
      (footprint "RESC2012X65N")
      (description "Resistor;  Thick Film;  Res 22 Ohms;  Pwr-Rtg0.125 W;  Tol 1%;  SMT;  0805")
      (fields
        (field (name "MANUFACTURER") "TE Connectivity")
        (field (name "MANUFACTURER PART NUMBER") "CRG0805F22R")
      )
      (libsource (lib "28Pin_Schlib") (part "CRG0805F22R"))
    )
    (comp (ref "R28")
      (value "22R")
      (footprint "RESC2012X65N")
      (description "Resistor;  Thick Film;  Res 22 Ohms;  Pwr-Rtg0.125 W;  Tol 1%;  SMT;  0805")
      (fields
        (field (name "MANUFACTURER") "TE Connectivity")
        (field (name "MANUFACTURER PART NUMBER") "CRG0805F22R")
      )
      (libsource (lib "28Pin_Schlib") (part "CRG0805F22R"))
    )
    (comp (ref "SW1")
      (value "1825910-6")
      (footprint "SW_ 1825910-6")
      (description "6X6, H5,  160G TAC.SWITCH")
      (fields (field (name "MANUFACTURER") "TE Connectivity Alcoswitch"))
      (libsource (lib "28Pin_Schlib") (part "1825910-6"))
    )
    (comp (ref "SW2")
      (value "1825910-6")
      (footprint "SW_ 1825910-6")
      (description "6X6, H5,  160G TAC.SWITCH")
      (fields (field (name "MANUFACTURER") "TE Connectivity Alcoswitch"))
      (libsource (lib "28Pin_Schlib") (part "1825910-6"))
    )
    (comp (ref "U1")
      (value "ATMEGA16U2-AU")
      (footprint "TQFP32")
      (description "MICROCHIP - ATMEGA16U2-AU - MCU, 8BIT, MEGAAVR, 16MHZ, TQFP-32")
      (fields (field (name "MANUFACTURER") "Microchip / Atmel"))
      (libsource (lib "28Pin_Schlib") (part "ATMEGA16U2-AU"))
    )
    (comp (ref "U2")
      (value "ATMEGA328P-PU")
      (footprint "DIP28_328P")
      (description "IC MCU 8BIT 32KB FLASH 28DIP")
      (fields (field (name "MANUFACTURER") "Microchip / Atmel"))
      (libsource (lib "28Pin_Schlib") (part "ATMEGA328P-PU"))
    )
    (comp (ref "U3")
      (value "TL1963A-33DCQR")
      (footprint "SOT127P706X180-6N")
      (fields
        (field (name "MF") "Texas Instruments")
        (field (name "DIGI-KEY_PART_NUMBER") "296-24534-1-ND")
        (field (name "BUYPART") "https://www.snapeda.com/parts/TL1963A-33DCQR/Texas%20Instruments/view-part/424520/?ref=eda")
      )
      (libsource (lib "TL1963A-33DCQR") (part "TL1963A-33DCQR"))
    )
    (comp (ref "U4")
      (value "SN74AHC1G09DBVR")
      (footprint "DBV_SOP_23_5")
      (description "TEXAS INSTRUMENTS - SN74AHC1G09DBVR - AND Gate, 74AHC1G09, 2 Input, 2 V to 5.5 V, SOT-23-5")
      (fields (field (name "MANUFACTURER") "Texas Instruments"))
      (libsource (lib "") (part "SN74AHC1G09DBVR_1"))
    )
    (comp (ref "U5")
      (value "SN74AHC1G09DBVR")
      (footprint "DBV_SOP_23_5")
      (description "TEXAS INSTRUMENTS - SN74AHC1G09DBVR - AND Gate, 74AHC1G09, 2 Input, 2 V to 5.5 V, SOT-23-5")
      (fields (field (name "MANUFACTURER") "Texas Instruments"))
      (libsource (lib "28Pin_Schlib") (part "SN74AHC1G09DBVR"))
    )
    (comp (ref "U6")
      (value "SN74AHC1G09DBVR")
      (footprint "DBV_SOP_23_5")
      (description "TEXAS INSTRUMENTS - SN74AHC1G09DBVR - AND Gate, 74AHC1G09, 2 Input, 2 V to 5.5 V, SOT-23-5")
      (fields (field (name "MANUFACTURER") "Texas Instruments"))
      (libsource (lib "28Pin_Schlib") (part "SN74AHC1G09DBVR"))
    )
    (comp (ref "U7")
      (value "SN74AHC1G09DBVR")
      (footprint "DBV_SOP_23_5")
      (description "TEXAS INSTRUMENTS - SN74AHC1G09DBVR - AND Gate, 74AHC1G09, 2 Input, 2 V to 5.5 V, SOT-23-5")
      (fields (field (name "MANUFACTURER") "Texas Instruments"))
      (libsource (lib "28Pin_Schlib") (part "SN74AHC1G09DBVR"))
    )
    (comp (ref "Y1")
      (value "ECS-160-S-23A-EN-TR")
      (footprint "CRYSTAL_16MHz")
      (description "16MHz Â±30ppm Crystal Series 60 Ohms 2-SMD, No Lead")
      (fields (field (name "MF") "ECS Inc."))
      (libsource (lib "SnapEDAsch") (part "ECS-160-S-23A-EN-TR"))
    )
    (comp (ref "Y2")
      (value "ECS-160-S-23A-EN-TR")
      (footprint "XTAL_ECS-160-S-23A-EN-TR")
      (description "16MHz Â±30ppm Crystal Series 60 Ohms 2-SMD, No Lead")
      (fields (field (name "MF") "ECS Inc."))
      (libsource (lib "ECS-160-S-23A-EN-TR(CRYSTAL)") (part "ECS-160-S-23A-EN-TR"))
    )
    (comp (ref "Z1")
      (value "CG0603MLU-05E")
      (footprint "R0603")
      (description "VARISTOR 0603")
      (fields (field (name "MANUFACTURER") "Bourns") (field (name "VOLTAGE") "5V"))
      (libsource (lib "28Pin_Schlib") (part "CG0603MLU-05E"))
    )
    (comp (ref "Z2")
      (value "CG0603MLU-05E")
      (footprint "R0603")
      (description "VARISTOR 0603")
      (fields (field (name "MANUFACTURER") "Bourns") (field (name "VOLTAGE") "5V"))
      (libsource (lib "28Pin_Schlib") (part "CG0603MLU-05E"))
    )
  )
  (nets
    (net (code "1") (name "+3V3") (class "Default")
      (node (ref "C12") (pin "1") (pinfunction "1_1") (pintype "passive"))
      (node (ref "C26") (pin "2") (pinfunction "2_2") (pintype "passive"))
      (node (ref "J11") (pin "1") (pinfunction "1_1") (pintype "passive"))
      (node (ref "J4") (pin "4") (pinfunction "4_4") (pintype "passive"))
      (node (ref "R19") (pin "2") (pinfunction "2_2") (pintype "passive"))
      (node (ref "U3") (pin "3") (pinfunction "OUT_3") (pintype "output"))
    )
    (net (code "2") (name "+5") (class "Default")
      (node (ref "C9") (pin "2") (pinfunction "2_2") (pintype "passive"))
      (node (ref "U1") (pin "31") (pinfunction "UVCC_31") (pintype "passive"))
    )
    (net (code "3") (name "+5V") (class "Default")
      (node (ref "C10") (pin "1") (pinfunction "1_1") (pintype "passive"))
      (node (ref "C25") (pin "2") (pinfunction "2_2") (pintype "passive"))
      (node (ref "C5") (pin "1") (pinfunction "1_1") (pintype "passive"))
      (node (ref "J11") (pin "3") (pinfunction "3_3") (pintype "passive"))
      (node (ref "J4") (pin "5") (pinfunction "5_5") (pintype "passive"))
      (node (ref "L1") (pin "2") (pinfunction "2_2") (pintype "passive"))
      (node (ref "R18") (pin "1") (pinfunction "1_1") (pintype "passive"))
      (node (ref "U3") (pin "1") (pinfunction "IN_1") (pintype "input"))
    )
    (net (code "4") (name "+5V{slash}3V3") (class "Default")
      (node (ref "C11") (pin "1") (pinfunction "1_1") (pintype "passive"))
      (node (ref "C13") (pin "2") (pinfunction "2_2") (pintype "passive"))
      (node (ref "C16") (pin "2") (pinfunction "2_2") (pintype "passive"))
      (node (ref "C22") (pin "2") (pinfunction "2_2") (pintype "passive"))
      (node (ref "C28") (pin "1") (pinfunction "1_1") (pintype "passive"))
      (node (ref "C29") (pin "1") (pinfunction "1_1") (pintype "passive"))
      (node (ref "C3") (pin "2") (pinfunction "2_2") (pintype "passive"))
      (node (ref "C30") (pin "1") (pinfunction "1_1") (pintype "passive"))
      (node (ref "D5") (pin "1") (pinfunction "1_1") (pintype "passive"))
      (node (ref "D6") (pin "1") (pinfunction "1_1") (pintype "passive"))
      (node (ref "FB1") (pin "1") (pinfunction "1_1") (pintype "passive"))
      (node (ref "FB2") (pin "1") (pinfunction "1_1") (pintype "passive"))
      (node (ref "FB3") (pin "1") (pinfunction "1_1") (pintype "passive"))
      (node (ref "J11") (pin "2") (pinfunction "2_2") (pintype "passive"))
      (node (ref "J2") (pin "2") (pinfunction "2_2") (pintype "passive"))
      (node (ref "J4") (pin "2") (pinfunction "2_2") (pintype "passive"))
      (node (ref "J7") (pin "2") (pinfunction "2_2") (pintype "passive"))
      (node (ref "R1") (pin "2") (pinfunction "2_2") (pintype "passive"))
      (node (ref "R15") (pin "2") (pinfunction "2_2") (pintype "passive"))
      (node (ref "R16") (pin "2") (pinfunction "2_2") (pintype "passive"))
      (node (ref "R17") (pin "2") (pinfunction "2_2") (pintype "passive"))
      (node (ref "R18") (pin "2") (pinfunction "2_2") (pintype "passive"))
      (node (ref "R19") (pin "1") (pinfunction "1_1") (pintype "passive"))
      (node (ref "R2") (pin "1") (pinfunction "1_1") (pintype "passive"))
      (node (ref "R21") (pin "2") (pinfunction "2_2") (pintype "passive"))
      (node (ref "R22") (pin "1") (pinfunction "1_1") (pintype "passive"))
      (node (ref "R23") (pin "1") (pinfunction "1_1") (pintype "passive"))
      (node (ref "R24") (pin "1") (pinfunction "1_1") (pintype "passive"))
      (node (ref "R3") (pin "1") (pinfunction "1_1") (pintype "passive"))
      (node (ref "R4") (pin "2") (pinfunction "2_2") (pintype "passive"))
      (node (ref "U4") (pin "5") (pinfunction "5_5") (pintype "passive"))
      (node (ref "U5") (pin "5") (pinfunction "5_5") (pintype "passive"))
      (node (ref "U6") (pin "5") (pinfunction "5_5") (pintype "passive"))
      (node (ref "U7") (pin "5") (pinfunction "5_5") (pintype "passive"))
    )
    (net (code "5") (name "+AREF") (class "Default")
      (node (ref "C17") (pin "2") (pinfunction "2_2") (pintype "passive"))
      (node (ref "C23") (pin "2") (pinfunction "2_2") (pintype "passive"))
      (node (ref "J8") (pin "8") (pinfunction "8_8") (pintype "passive"))
      (node (ref "U2") (pin "21") (pinfunction "AREF_21") (pintype "passive"))
    )
    (net (code "6") (name "/+3V3_16U2_UCAP") (class "Default")
      (node (ref "C15") (pin "2") (pinfunction "2_2") (pintype "passive"))
      (node (ref "R13") (pin "1") (pinfunction "1_1") (pintype "passive"))
      (node (ref "U1") (pin "27") (pinfunction "UCAP_27") (pintype "passive"))
    )
    (net (code "7") (name "/+5V_USB") (class "Default")
      (node (ref "C4") (pin "1") (pinfunction "1_1") (pintype "passive"))
      (node (ref "J5") (pin "1") (pinfunction "1_1") (pintype "passive"))
      (node (ref "L1") (pin "1") (pinfunction "1_1") (pintype "passive"))
    )
    (net (code "8") (name "/+5V{slash}3V3_16U2") (class "Default")
      (node (ref "C6") (pin "2") (pinfunction "2_2") (pintype "passive"))
      (node (ref "C7") (pin "2") (pinfunction "2_2") (pintype "passive"))
      (node (ref "C8") (pin "2") (pinfunction "2_2") (pintype "passive"))
      (node (ref "FB1") (pin "2") (pinfunction "2_2") (pintype "passive"))
      (node (ref "R13") (pin "2") (pinfunction "2_2") (pintype "passive"))
      (node (ref "U1") (pin "32") (pinfunction "AVCC_32") (pintype "passive"))
      (node (ref "U1") (pin "4") (pinfunction "VCC_4") (pintype "passive"))
    )
    (net (code "9") (name "/+5V{slash}3V3_328P_AVCC") (class "Default")
      (node (ref "C20") (pin "2") (pinfunction "2_2") (pintype "passive"))
      (node (ref "C21") (pin "2") (pinfunction "2_2") (pintype "passive"))
      (node (ref "FB3") (pin "2") (pinfunction "2_2") (pintype "passive"))
      (node (ref "U2") (pin "20") (pinfunction "AVCC_20") (pintype "passive"))
    )
    (net (code "10") (name "/+5V{slash}3V3_328P_VCC") (class "Default")
      (node (ref "C18") (pin "2") (pinfunction "2_2") (pintype "passive"))
      (node (ref "C19") (pin "2") (pinfunction "2_2") (pintype "passive"))
      (node (ref "FB2") (pin "2") (pinfunction "2_2") (pintype "passive"))
      (node (ref "U2") (pin "7") (pinfunction "VCC_7") (pintype "passive"))
    )
    (net (code "11") (name "/16U2PROG_328P_RESETn") (class "Default")
      (node (ref "J6") (pin "2") (pinfunction "2_2") (pintype "passive"))
      (node (ref "R1") (pin "1") (pinfunction "1_1") (pintype "passive"))
      (node (ref "U1") (pin "13") (pinfunction "/_HWB_/_AIN6_/_T0_/_INT7)_PD7_13") (pintype "passive"))
    )
    (net (code "12") (name "/16U2_16MHZ_XTAL1") (class "Default")
      (node (ref "C2") (pin "2") (pinfunction "2_2") (pintype "passive"))
      (node (ref "R5") (pin "1") (pinfunction "1_1") (pintype "passive"))
      (node (ref "U1") (pin "2") (pinfunction "(PC0)_XTAL2_2") (pintype "passive"))
      (node (ref "Y1") (pin "1") (pinfunction "IN/OUT_1") (pintype "passive"))
    )
    (net (code "13") (name "/16U2_16MHZ_XTAL2") (class "Default")
      (node (ref "C1") (pin "2") (pinfunction "2_2") (pintype "passive"))
      (node (ref "R5") (pin "2") (pinfunction "2_2") (pintype "passive"))
      (node (ref "U1") (pin "1") (pinfunction "XTAL1_1") (pintype "passive"))
      (node (ref "Y1") (pin "2") (pinfunction "OUT/IN_2") (pintype "passive"))
    )
    (net (code "14") (name "/16U2_BUF_RESETn") (class "Default")
      (node (ref "C33") (pin "2") (pinfunction "2_2") (pintype "passive"))
      (node (ref "R28") (pin "2") (pinfunction "2_2") (pintype "passive"))
      (node (ref "U7") (pin "1") (pinfunction "1_1") (pintype "passive"))
      (node (ref "U7") (pin "2") (pinfunction "2_2") (pintype "passive"))
    )
    (net (code "16") (name "/16U2_MISO") (class "Default")
      (node (ref "J2") (pin "1") (pinfunction "1_1") (pintype "passive"))
      (node (ref "U1") (pin "17") (pinfunction "(PDO_/_MISO_/_PCINT3)_PB3_17") (pintype "passive"))
    )
    (net (code "17") (name "/16U2_MOSI") (class "Default")
      (node (ref "J2") (pin "4") (pinfunction "4_4") (pintype "passive"))
      (node (ref "U1") (pin "16") (pinfunction "(PDI_/_MOSI_/_PCINT2)_PB2_16") (pintype "passive"))
    )
    (net (code "18") (name "/16U2_PB4") (class "Default")
      (node (ref "J1") (pin "1") (pinfunction "1_1") (pintype "passive"))
      (node (ref "J3") (pin "2") (pinfunction "2_2") (pintype "passive"))
      (node (ref "U1") (pin "18") (pinfunction "(T1_/_PCINT4)_PB4_18") (pintype "passive"))
    )
    (net (code "19") (name "/16U2_PB5") (class "Default")
      (node (ref "J1") (pin "3") (pinfunction "3_3") (pintype "passive"))
      (node (ref "U1") (pin "19") (pinfunction "(PCINT5)_PB5_19") (pintype "passive"))
    )
    (net (code "20") (name "/16U2_PB6") (class "Default")
      (node (ref "J1") (pin "2") (pinfunction "2_2") (pintype "passive"))
      (node (ref "U1") (pin "20") (pinfunction "(PCINT6)_PB6_20") (pintype "passive"))
    )
    (net (code "21") (name "/16U2_PB7") (class "Default")
      (node (ref "J1") (pin "4") (pinfunction "4_4") (pintype "passive"))
      (node (ref "U1") (pin "21") (pinfunction "(PCINT7_/_OC.0A_/_OC.1C)_PB7_21") (pintype "passive"))
    )
    (net (code "22") (name "/16U2_RESETn") (class "Default")
      (node (ref "J3") (pin "4") (pinfunction "4_4") (pintype "passive"))
      (node (ref "R4") (pin "1") (pinfunction "1_1") (pintype "passive"))
      (node (ref "U1") (pin "24") (pinfunction "~{RESET}_(PC1_/_dW)_24") (pintype "passive"))
      (node (ref "U7") (pin "4") (pinfunction "4_4") (pintype "passive"))
    )
    (net (code "23") (name "/16U2_RXD") (class "Default")
      (node (ref "R11") (pin "1") (pinfunction "1_1") (pintype "passive"))
      (node (ref "U1") (pin "8") (pinfunction "(RXD1_/_AIN1_/_INT2)_PD2_8") (pintype "passive"))
    )
    (net (code "24") (name "/16U2_Rx_LED") (class "Default")
      (node (ref "D2") (pin "2") (pinfunction "K_2") (pintype "passive"))
      (node (ref "U1") (pin "10") (pinfunction "(INT5/_AIN3)_PD4_10") (pintype "passive"))
    )
    (net (code "25") (name "/16U2_SCLK") (class "Default")
      (node (ref "J2") (pin "3") (pinfunction "3_3") (pintype "passive"))
      (node (ref "R6") (pin "2") (pinfunction "2_2") (pintype "passive"))
    )
    (net (code "26") (name "/16U2_SCLK_R") (class "Default")
      (node (ref "R6") (pin "1") (pinfunction "1_1") (pintype "passive"))
      (node (ref "U1") (pin "15") (pinfunction "(SCLK_/_PCINT1)_PB1_15") (pintype "passive"))
    )
    (net (code "27") (name "/16U2_TXD") (class "Default")
      (node (ref "R8") (pin "1") (pinfunction "1_1") (pintype "passive"))
      (node (ref "U1") (pin "9") (pinfunction "(TXD1_/_INT3)_PD3_9") (pintype "passive"))
    )
    (net (code "28") (name "/16U2_Tx_LED") (class "Default")
      (node (ref "D1") (pin "2") (pinfunction "K_2") (pintype "passive"))
      (node (ref "U1") (pin "11") (pinfunction "(XCK_AIN4_/_PCINT12)_PD5_11") (pintype "passive"))
    )
    (net (code "29") (name "/328P RESETn") (class "Default")
      (node (ref "J10") (pin "2") (pinfunction "2_2") (pintype "passive"))
      (node (ref "J4") (pin "3") (pinfunction "3_3") (pintype "passive"))
      (node (ref "R11") (pin "2") (pinfunction "2_2") (pintype "passive"))
      (node (ref "R15") (pin "1") (pinfunction "1_1") (pintype "passive"))
      (node (ref "U2") (pin "1") (pinfunction "PC6_(PCINT14/~{RESE}T)_1") (pintype "passive"))
      (node (ref "U2") (pin "3") (pinfunction "(PCINT17/TXD)_PD1_3") (pintype "passive"))
    )
    (net (code "30") (name "/328P_16MHZ_XTAL1") (class "Default")
      (node (ref "C27") (pin "2") (pinfunction "2_2") (pintype "passive"))
      (node (ref "R20") (pin "1") (pinfunction "1_1") (pintype "passive"))
      (node (ref "U2") (pin "10") (pinfunction "PB7_(PCINT7/XTAL2/TOSC2)_10") (pintype "passive"))
      (node (ref "Y2") (pin "1") (pinfunction "IN/OUT_1") (pintype "passive"))
    )
    (net (code "31") (name "/328P_16MHZ_XTAL2") (class "Default")
      (node (ref "C24") (pin "2") (pinfunction "2_2") (pintype "passive"))
      (node (ref "R20") (pin "2") (pinfunction "2_2") (pintype "passive"))
      (node (ref "U2") (pin "9") (pinfunction "PB6_(PCINT6/XTAL1/TOSC1)_9") (pintype "passive"))
      (node (ref "Y2") (pin "2") (pinfunction "OUT/IN_2") (pintype "passive"))
    )
    (net (code "32") (name "/328P_AUTORESETn") (class "Default")
      (node (ref "C14") (pin "1") (pinfunction "1_1") (pintype "passive"))
      (node (ref "R21") (pin "1") (pinfunction "1_1") (pintype "passive"))
      (node (ref "U6") (pin "1") (pinfunction "1_1") (pintype "passive"))
    )
    (net (code "33") (name "/328P_BUF_RESETn") (class "Default")
      (node (ref "C32") (pin "2") (pinfunction "2_2") (pintype "passive"))
      (node (ref "R27") (pin "2") (pinfunction "2_2") (pintype "passive"))
      (node (ref "U6") (pin "2") (pinfunction "2_2") (pintype "passive"))
    )
    (net (code "34") (name "/328P_RESETn") (class "Default")
      (node (ref "J3") (pin "1") (pinfunction "1_1") (pintype "passive"))
      (node (ref "U6") (pin "4") (pinfunction "4_4") (pintype "passive"))
    )
    (net (code "35") (name "/AD0") (class "Default")
      (node (ref "J9") (pin "1") (pinfunction "1_1") (pintype "passive"))
      (node (ref "U2") (pin "23") (pinfunction "(ADC0/PCINT8)_PC0_23") (pintype "passive"))
    )
    (net (code "36") (name "/AD1") (class "Default")
      (node (ref "J9") (pin "2") (pinfunction "2_2") (pintype "passive"))
      (node (ref "U2") (pin "24") (pinfunction "_(ADC1/PCINT9)_PC1_24") (pintype "passive"))
    )
    (net (code "37") (name "/AD2") (class "Default")
      (node (ref "J9") (pin "3") (pinfunction "3_3") (pintype "passive"))
      (node (ref "U2") (pin "25") (pinfunction "(ADC2/PCINT10)_PC2_25") (pintype "passive"))
    )
    (net (code "38") (name "/AD3") (class "Default")
      (node (ref "J9") (pin "4") (pinfunction "4_4") (pintype "passive"))
      (node (ref "U2") (pin "26") (pinfunction "(ADC3/PCINT11)_PC3_26") (pintype "passive"))
    )
    (net (code "39") (name "/AD4{slash}SDA") (class "Default")
      (node (ref "J8") (pin "9") (pinfunction "9_9") (pintype "passive"))
      (node (ref "J9") (pin "5") (pinfunction "5_5") (pintype "passive"))
      (node (ref "U2") (pin "27") (pinfunction "(ADC4/SDA/PCINT12)_PC4_27") (pintype "passive"))
    )
    (net (code "40") (name "/AD5{slash}SCL") (class "Default")
      (node (ref "J8") (pin "10") (pinfunction "10_10") (pintype "passive"))
      (node (ref "J9") (pin "6") (pinfunction "6_6") (pintype "passive"))
      (node (ref "U2") (pin "28") (pinfunction "(ADC5/SCL/PCINT13)_PC5_28") (pintype "passive"))
    )
    (net (code "41") (name "/BUTTON_RESETn") (class "Default")
      (node (ref "D5") (pin "2") (pinfunction "2_2") (pintype "passive"))
      (node (ref "R22") (pin "2") (pinfunction "2_2") (pintype "passive"))
      (node (ref "R23") (pin "2") (pinfunction "2_2") (pintype "passive"))
      (node (ref "R26") (pin "1") (pinfunction "1_1") (pintype "passive"))
      (node (ref "R27") (pin "1") (pinfunction "1_1") (pintype "passive"))
      (node (ref "SW1") (pin "3") (pinfunction "3_3") (pintype "passive"))
      (node (ref "SW1") (pin "4") (pinfunction "4_4") (pintype "passive"))
      (node (ref "SW2") (pin "3") (pinfunction "3_3") (pintype "passive"))
      (node (ref "SW2") (pin "4") (pinfunction "4_4") (pintype "passive"))
    )
    (net (code "42") (name "/CON_USB_N") (class "Default")
      (node (ref "J5") (pin "2") (pinfunction "2_2") (pintype "passive"))
      (node (ref "R7") (pin "1") (pinfunction "1_1") (pintype "passive"))
      (node (ref "Z1") (pin "1") (pinfunction "1_1") (pintype "passive"))
    )
    (net (code "43") (name "/CON_USB_P") (class "Default")
      (node (ref "J5") (pin "3") (pinfunction "3_3") (pintype "passive"))
      (node (ref "R10") (pin "1") (pinfunction "1_1") (pintype "passive"))
      (node (ref "Z2") (pin "1") (pinfunction "1_1") (pintype "passive"))
    )
    (net (code "44") (name "/IO0") (class "Default")
      (node (ref "J10") (pin "1") (pinfunction "1_1") (pintype "passive"))
      (node (ref "J7") (pin "5") (pinfunction "5_5") (pintype "passive"))
      (node (ref "R8") (pin "2") (pinfunction "2_2") (pintype "passive"))
      (node (ref "U2") (pin "2") (pinfunction "(PCINT16/RXD)_PD0_2") (pintype "passive"))
    )
    (net (code "45") (name "/IO2") (class "Default")
      (node (ref "J10") (pin "3") (pinfunction "3_3") (pintype "passive"))
      (node (ref "U2") (pin "4") (pinfunction "(PCINT18/INT0)_PD2_4") (pintype "passive"))
    )
    (net (code "46") (name "/IO3") (class "Default")
      (node (ref "J10") (pin "4") (pinfunction "4_4") (pintype "passive"))
      (node (ref "U2") (pin "5") (pinfunction "(PCINT19/OC2B/INT1)_PD3_5") (pintype "passive"))
    )
    (net (code "47") (name "/IO4") (class "Default")
      (node (ref "J10") (pin "5") (pinfunction "5_5") (pintype "passive"))
      (node (ref "U2") (pin "6") (pinfunction "(PCINT20/XCK/T0)_PD4_6") (pintype "passive"))
    )
    (net (code "48") (name "/IO5") (class "Default")
      (node (ref "J10") (pin "6") (pinfunction "6_6") (pintype "passive"))
      (node (ref "U2") (pin "11") (pinfunction "(PCINT21/OC0B/T1)_PD5_11") (pintype "passive"))
    )
    (net (code "49") (name "/IO6") (class "Default")
      (node (ref "J10") (pin "7") (pinfunction "7_7") (pintype "passive"))
      (node (ref "U2") (pin "12") (pinfunction "(PCINT22/OC0A/AIN0)_PD6_12") (pintype "passive"))
    )
    (net (code "50") (name "/IO7") (class "Default")
      (node (ref "J10") (pin "8") (pinfunction "8_8") (pintype "passive"))
      (node (ref "U2") (pin "13") (pinfunction "(PCINT23/AIN1)_PD7_13") (pintype "passive"))
    )
    (net (code "51") (name "/IO8") (class "Default")
      (node (ref "J8") (pin "1") (pinfunction "1_1") (pintype "passive"))
      (node (ref "R25") (pin "2") (pinfunction "2_2") (pintype "passive"))
      (node (ref "U2") (pin "14") (pinfunction "(PCINT0/CLKO/ICP1)_PB0_14") (pintype "passive"))
    )
    (net (code "52") (name "/IO9") (class "Default")
      (node (ref "J8") (pin "2") (pinfunction "2_2") (pintype "passive"))
      (node (ref "U2") (pin "15") (pinfunction "_(OC1A/PCINT1)_PB1_15") (pintype "passive"))
    )
    (net (code "53") (name "/MISO") (class "Default")
      (node (ref "J7") (pin "1") (pinfunction "1_1") (pintype "passive"))
      (node (ref "J8") (pin "5") (pinfunction "5_5") (pintype "passive"))
      (node (ref "U2") (pin "18") (pinfunction "(MISO/PCINT4)_PB4_18") (pintype "passive"))
    )
    (net (code "54") (name "/MOSI") (class "Default")
      (node (ref "J7") (pin "4") (pinfunction "4_4") (pintype "passive"))
      (node (ref "J8") (pin "4") (pinfunction "4_4") (pintype "passive"))
      (node (ref "U2") (pin "17") (pinfunction "_(MOSI/OC2A/PCINT3)_PB3_17") (pintype "passive"))
    )
    (net (code "55") (name "/SCK") (class "Default")
      (node (ref "J7") (pin "3") (pinfunction "3_3") (pintype "passive"))
      (node (ref "J8") (pin "6") (pinfunction "6_6") (pintype "passive"))
      (node (ref "R14") (pin "2") (pinfunction "2_2") (pintype "passive"))
      (node (ref "U4") (pin "1") (pinfunction "1_1") (pintype "passive"))
      (node (ref "U4") (pin "2") (pinfunction "2_2") (pintype "passive"))
    )
    (net (code "56") (name "/SCK_R") (class "Default")
      (node (ref "R14") (pin "1") (pinfunction "1_1") (pintype "passive"))
      (node (ref "U2") (pin "19") (pinfunction "(SCK/PCINT5)_PB5_19") (pintype "passive"))
    )
    (net (code "57") (name "/SS") (class "Default")
      (node (ref "J8") (pin "3") (pinfunction "3_3") (pintype "passive"))
      (node (ref "U2") (pin "16") (pinfunction "_(SS/OC1B/PCINT2)_PB2_16") (pintype "passive"))
    )
    (net (code "58") (name "/USB_N") (class "Default")
      (node (ref "R7") (pin "2") (pinfunction "2_2") (pintype "passive"))
      (node (ref "U1") (pin "30") (pinfunction "D-_30") (pintype "passive"))
    )
    (net (code "59") (name "/USB_P") (class "Default")
      (node (ref "R10") (pin "2") (pinfunction "2_2") (pintype "passive"))
      (node (ref "U1") (pin "29") (pinfunction "D+_29") (pintype "passive"))
    )
    (net (code "60") (name "/USER_BUTTON_BUF") (class "Default")
      (node (ref "C31") (pin "2") (pinfunction "2_2") (pintype "passive"))
      (node (ref "R26") (pin "2") (pinfunction "2_2") (pintype "passive"))
      (node (ref "U5") (pin "1") (pinfunction "1_1") (pintype "passive"))
      (node (ref "U5") (pin "2") (pinfunction "2_2") (pintype "passive"))
    )
    (net (code "61") (name "GND") (class "Default")
      (node (ref "C1") (pin "1") (pinfunction "1_1") (pintype "passive"))
      (node (ref "C10") (pin "2") (pinfunction "2_2") (pintype "passive"))
      (node (ref "C11") (pin "2") (pinfunction "2_2") (pintype "passive"))
      (node (ref "C12") (pin "2") (pinfunction "2_2") (pintype "passive"))
      (node (ref "C13") (pin "1") (pinfunction "1_1") (pintype "passive"))
      (node (ref "C15") (pin "1") (pinfunction "1_1") (pintype "passive"))
      (node (ref "C16") (pin "1") (pinfunction "1_1") (pintype "passive"))
      (node (ref "C17") (pin "1") (pinfunction "1_1") (pintype "passive"))
      (node (ref "C18") (pin "1") (pinfunction "1_1") (pintype "passive"))
      (node (ref "C19") (pin "1") (pinfunction "1_1") (pintype "passive"))
      (node (ref "C2") (pin "1") (pinfunction "1_1") (pintype "passive"))
      (node (ref "C20") (pin "1") (pinfunction "1_1") (pintype "passive"))
      (node (ref "C21") (pin "1") (pinfunction "1_1") (pintype "passive"))
      (node (ref "C22") (pin "1") (pinfunction "1_1") (pintype "passive"))
      (node (ref "C23") (pin "1") (pinfunction "1_1") (pintype "passive"))
      (node (ref "C24") (pin "1") (pinfunction "1_1") (pintype "passive"))
      (node (ref "C25") (pin "1") (pinfunction "1_1") (pintype "passive"))
      (node (ref "C26") (pin "1") (pinfunction "1_1") (pintype "passive"))
      (node (ref "C27") (pin "1") (pinfunction "1_1") (pintype "passive"))
      (node (ref "C28") (pin "2") (pinfunction "2_2") (pintype "passive"))
      (node (ref "C29") (pin "2") (pinfunction "2_2") (pintype "passive"))
      (node (ref "C3") (pin "1") (pinfunction "1_1") (pintype "passive"))
      (node (ref "C30") (pin "2") (pinfunction "2_2") (pintype "passive"))
      (node (ref "C31") (pin "1") (pinfunction "1_1") (pintype "passive"))
      (node (ref "C32") (pin "1") (pinfunction "1_1") (pintype "passive"))
      (node (ref "C33") (pin "1") (pinfunction "1_1") (pintype "passive"))
      (node (ref "C4") (pin "2") (pinfunction "2_2") (pintype "passive"))
      (node (ref "C5") (pin "2") (pinfunction "2_2") (pintype "passive"))
      (node (ref "C6") (pin "1") (pinfunction "1_1") (pintype "passive"))
      (node (ref "C7") (pin "1") (pinfunction "1_1") (pintype "passive"))
      (node (ref "C8") (pin "1") (pinfunction "1_1") (pintype "passive"))
      (node (ref "C9") (pin "1") (pinfunction "1_1") (pintype "passive"))
      (node (ref "D4") (pin "2") (pinfunction "K_2") (pintype "passive"))
      (node (ref "J2") (pin "6") (pinfunction "6_6") (pintype "passive"))
      (node (ref "J4") (pin "6") (pinfunction "6_6") (pintype "passive"))
      (node (ref "J4") (pin "7") (pinfunction "7_7") (pintype "passive"))
      (node (ref "J5") (pin "10") (pinfunction "10_10") (pintype "passive"))
      (node (ref "J5") (pin "11") (pinfunction "11_11") (pintype "passive"))
      (node (ref "J5") (pin "5") (pinfunction "5_5") (pintype "passive"))
      (node (ref "J5") (pin "6") (pinfunction "6_6") (pintype "passive"))
      (node (ref "J5") (pin "7") (pinfunction "7_7") (pintype "passive"))
      (node (ref "J5") (pin "8") (pinfunction "8_8") (pintype "passive"))
      (node (ref "J5") (pin "9") (pinfunction "9_9") (pintype "passive"))
      (node (ref "J7") (pin "6") (pinfunction "6_6") (pintype "passive"))
      (node (ref "J8") (pin "7") (pinfunction "7_7") (pintype "passive"))
      (node (ref "MH1") (pin "1") (pinfunction "1_1") (pintype "passive"))
      (node (ref "MH2") (pin "1") (pinfunction "1_1") (pintype "passive"))
      (node (ref "MH3") (pin "1") (pinfunction "1_1") (pintype "passive"))
      (node (ref "R12") (pin "1") (pinfunction "1_1") (pintype "passive"))
      (node (ref "R9") (pin "2") (pinfunction "2_2") (pintype "passive"))
      (node (ref "SW1") (pin "1") (pinfunction "1_1") (pintype "passive"))
      (node (ref "SW1") (pin "2") (pinfunction "2_2") (pintype "passive"))
      (node (ref "SW2") (pin "1") (pinfunction "1_1") (pintype "passive"))
      (node (ref "SW2") (pin "2") (pinfunction "2_2") (pintype "passive"))
      (node (ref "U1") (pin "28") (pinfunction "UGND_28") (pintype "passive"))
      (node (ref "U1") (pin "3") (pinfunction "GND_3") (pintype "passive"))
      (node (ref "U2") (pin "22") (pinfunction "GND_22") (pintype "passive"))
      (node (ref "U2") (pin "8") (pinfunction "GND_8") (pintype "passive"))
      (node (ref "U3") (pin "2") (pinfunction "GND_2") (pintype "power_in"))
      (node (ref "U3") (pin "4") (pinfunction "GND_4") (pintype "power_in"))
      (node (ref "U4") (pin "3") (pinfunction "3_3") (pintype "passive"))
      (node (ref "U5") (pin "3") (pinfunction "3_3") (pintype "passive"))
      (node (ref "U6") (pin "3") (pinfunction "3_3") (pintype "passive"))
      (node (ref "U7") (pin "3") (pinfunction "3_3") (pintype "passive"))
      (node (ref "Z1") (pin "2") (pinfunction "2_2") (pintype "passive"))
      (node (ref "Z2") (pin "2") (pinfunction "2_2") (pintype "passive"))
    )
    (net (code "62") (name "Net-(C14-Pad2)") (class "Default")
      (node (ref "C14") (pin "2") (pinfunction "2_2") (pintype "passive"))
      (node (ref "J6") (pin "1") (pinfunction "1_1") (pintype "passive"))
    )
    (net (code "63") (name "Net-(D1-A)") (class "Default")
      (node (ref "D1") (pin "1") (pinfunction "A_1") (pintype "passive"))
      (node (ref "R2") (pin "2") (pinfunction "2_2") (pintype "passive"))
    )
    (net (code "64") (name "Net-(D2-A)") (class "Default")
      (node (ref "D2") (pin "1") (pinfunction "A_1") (pintype "passive"))
      (node (ref "R3") (pin "2") (pinfunction "2_2") (pintype "passive"))
    )
    (net (code "65") (name "Net-(D3-A)") (class "Default")
      (node (ref "D3") (pin "1") (pinfunction "A_1") (pintype "passive"))
      (node (ref "R17") (pin "1") (pinfunction "1_1") (pintype "passive"))
    )
    (net (code "66") (name "Net-(D3-K)") (class "Default")
      (node (ref "D3") (pin "2") (pinfunction "K_2") (pintype "passive"))
      (node (ref "U4") (pin "4") (pinfunction "4_4") (pintype "passive"))
    )
    (net (code "67") (name "Net-(D4-A)") (class "Default")
      (node (ref "D4") (pin "1") (pinfunction "A_1") (pintype "passive"))
      (node (ref "R16") (pin "1") (pinfunction "1_1") (pintype "passive"))
    )
    (net (code "68") (name "Net-(D6-Pad2)") (class "Default")
      (node (ref "D6") (pin "2") (pinfunction "2_2") (pintype "passive"))
      (node (ref "R24") (pin "2") (pinfunction "2_2") (pintype "passive"))
      (node (ref "R28") (pin "1") (pinfunction "1_1") (pintype "passive"))
    )
    (net (code "69") (name "Net-(J2-Pad5)") (class "Default")
      (node (ref "J2") (pin "5") (pinfunction "5_5") (pintype "passive"))
      (node (ref "J3") (pin "3") (pinfunction "3_3") (pintype "passive"))
    )
    (net (code "70") (name "Net-(J5-Pad4)") (class "Default")
      (node (ref "J5") (pin "4") (pinfunction "4_4") (pintype "passive"))
      (node (ref "R9") (pin "1") (pinfunction "1_1") (pintype "passive"))
    )
    (net (code "71") (name "Net-(J6-Pad3)") (class "Default")
      (node (ref "J6") (pin "3") (pinfunction "3_3") (pintype "passive"))
      (node (ref "R12") (pin "2") (pinfunction "2_2") (pintype "passive"))
    )
    (net (code "72") (name "Net-(R25-Pad1)") (class "Default")
      (node (ref "R25") (pin "1") (pinfunction "1_1") (pintype "passive"))
      (node (ref "U5") (pin "4") (pinfunction "4_4") (pintype "passive"))
    )
    (net (code "73") (name "unconnected-(J4-Pad1)") (class "Default")
      (node (ref "J4") (pin "1") (pinfunction "1_1") (pintype "passive+no_connect"))
    )
    (net (code "74") (name "unconnected-(J4-Pad8)") (class "Default")
      (node (ref "J4") (pin "8") (pinfunction "8_8") (pintype "passive+no_connect"))
    )
    (net (code "75") (name "unconnected-(MH4-Pad1)") (class "Default")
      (node (ref "MH4") (pin "1") (pinfunction "1_1") (pintype "passive+no_connect"))
    )
    (net (code "76") (name "unconnected-(U1-(AIN0_{slash}_INT1)_PD1-Pad7)") (class "Default")
      (node (ref "U1") (pin "7") (pinfunction "(AIN0_/_INT1)_PD1_7") (pintype "passive+no_connect"))
    )
    (net (code "77") (name "unconnected-(U1-(INT4_{slash}_ICP1_{slash}_CLKO)PC7-Pad22)") (class "Default")
      (node (ref "U1") (pin "22") (pinfunction "(INT4_/_ICP1_/_CLKO)PC7_22") (pintype "passive+no_connect"))
    )
    (net (code "78") (name "unconnected-(U1-(OC.0B_{slash}_INT0)_PD0-Pad6)") (class "Default")
      (node (ref "U1") (pin "6") (pinfunction "(OC.0B_/_INT0)_PD0_6") (pintype "passive+no_connect"))
    )
    (net (code "79") (name "unconnected-(U1-(OC.1A_{slash}_PCINT8)PC6-Pad23)") (class "Default")
      (node (ref "U1") (pin "23") (pinfunction "(OC.1A_/_PCINT8)PC6_23") (pintype "passive+no_connect"))
    )
    (net (code "80") (name "unconnected-(U1-(PCINT10)PC4-Pad26)") (class "Default")
      (node (ref "U1") (pin "26") (pinfunction "(PCINT10)PC4_26") (pintype "passive+no_connect"))
    )
    (net (code "81") (name "unconnected-(U1-(PCINT11_{slash}AIN2_)_PC2-Pad5)") (class "Default")
      (node (ref "U1") (pin "5") (pinfunction "(PCINT11_/AIN2_)_PC2_5") (pintype "passive+no_connect"))
    )
    (net (code "82") (name "unconnected-(U1-(RTS_{slash}_AIN5_{slash}_INT6)_PD6-Pad12)") (class "Default")
      (node (ref "U1") (pin "12") (pinfunction "(RTS_/_AIN5_/_INT6)_PD6_12") (pintype "passive"))
    )
    (net (code "83") (name "unconnected-(U1-(SS_{slash}_PCINT0)_PB0-Pad14)") (class "Default")
      (node (ref "U1") (pin "14") (pinfunction "(SS_/_PCINT0)_PB0_14") (pintype "passive+no_connect"))
    )
    (net (code "84") (name "unconnected-(U1-(_PCINT9{slash}_OC.1B)PC5-Pad25)") (class "Default")
      (node (ref "U1") (pin "25") (pinfunction "(_PCINT9/_OC.1B)PC5_25") (pintype "passive+no_connect"))
    )
  )
)
